# MotherboardRev1.net
KiCad netlist of a schematic drawn in EAGLE
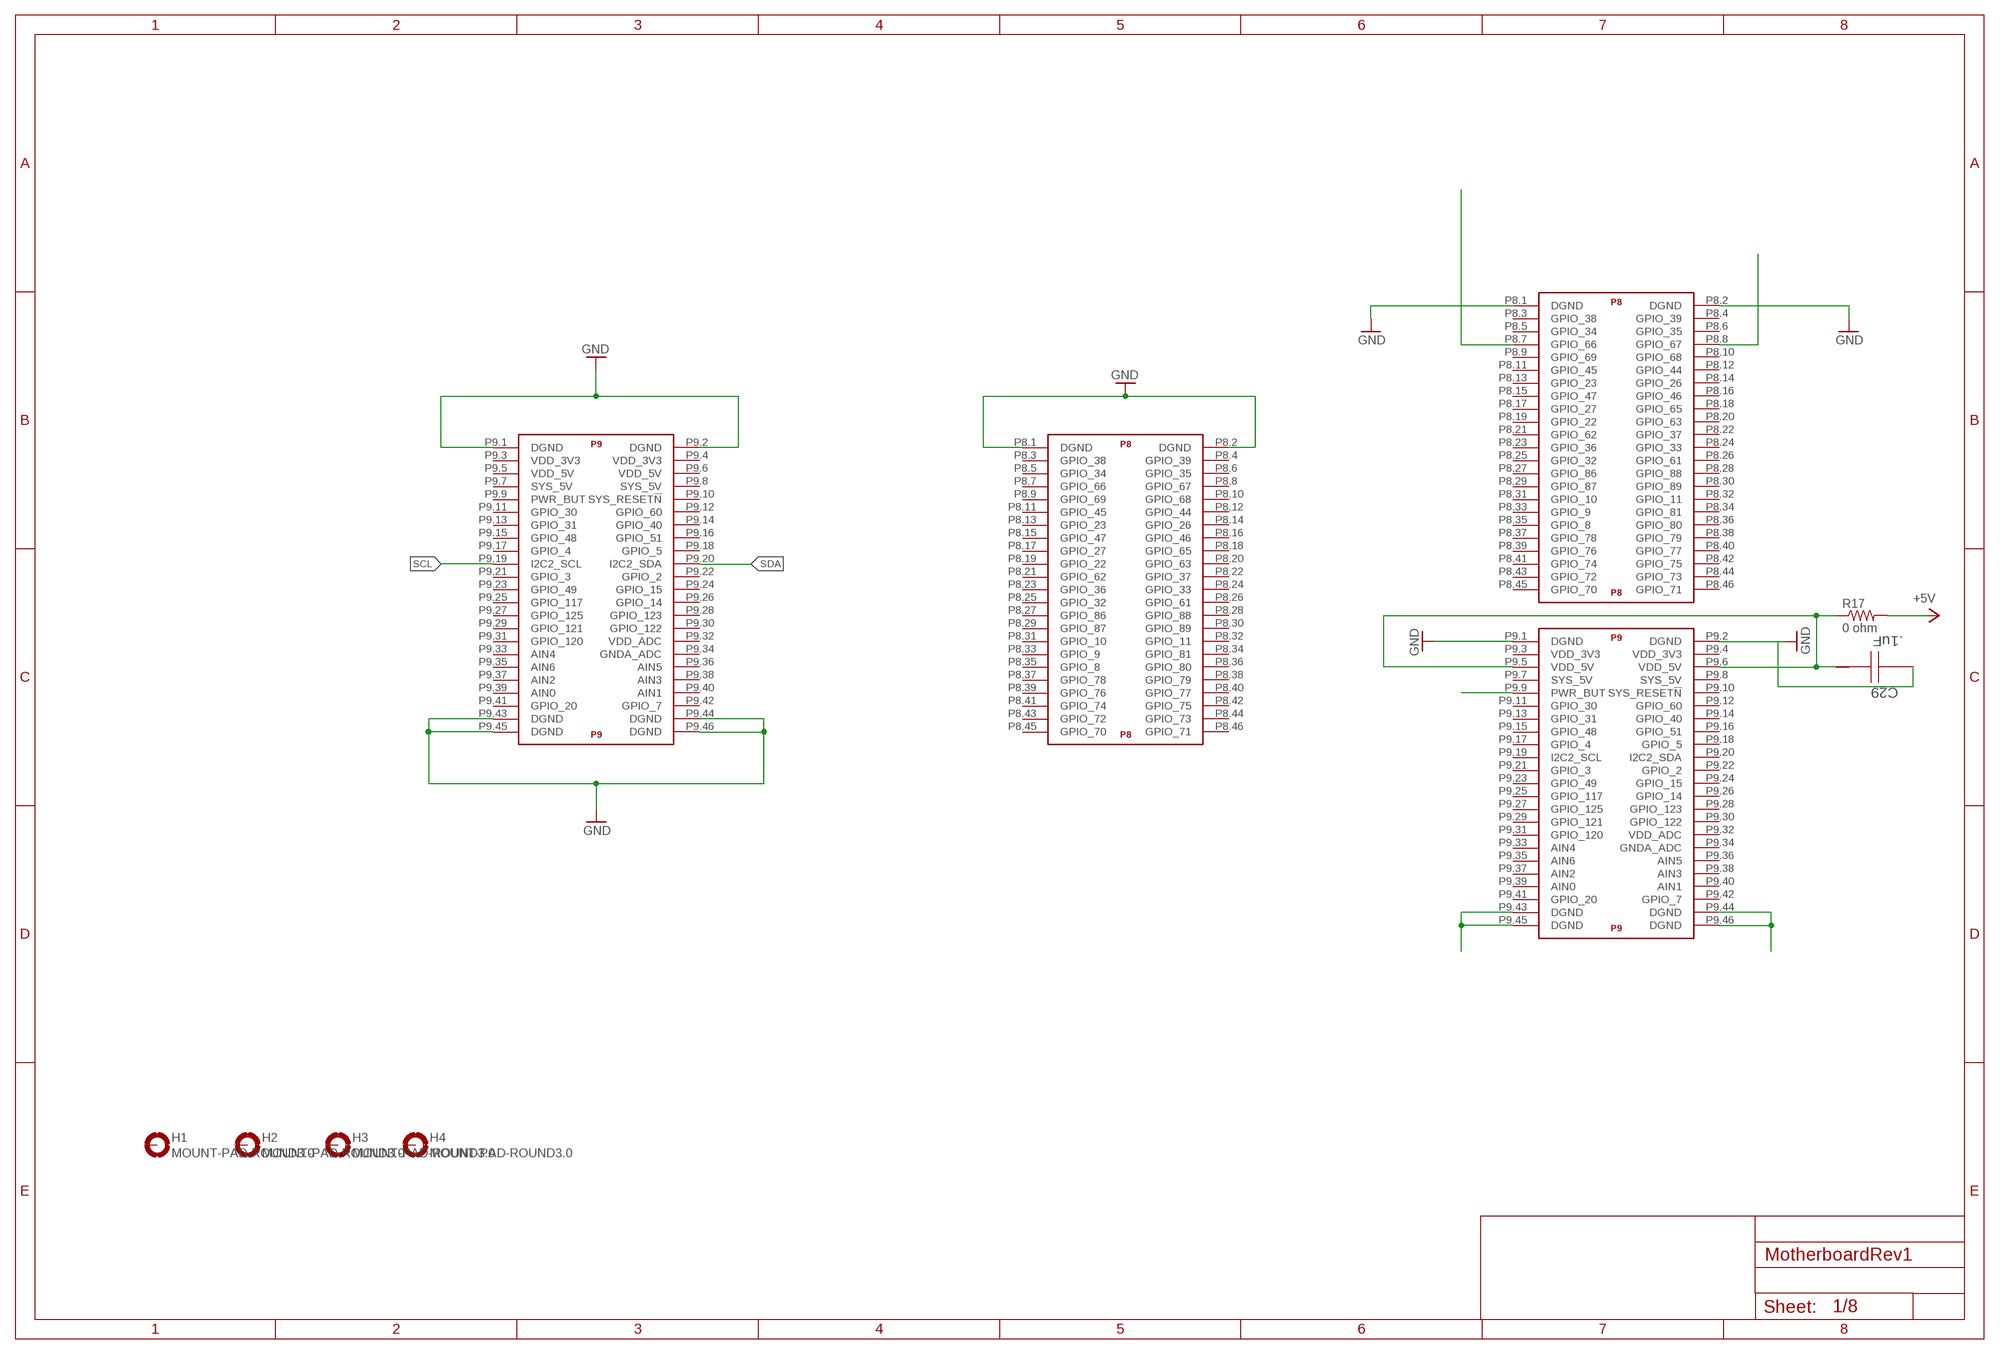
[diagram p0: schematic, sheet 1]
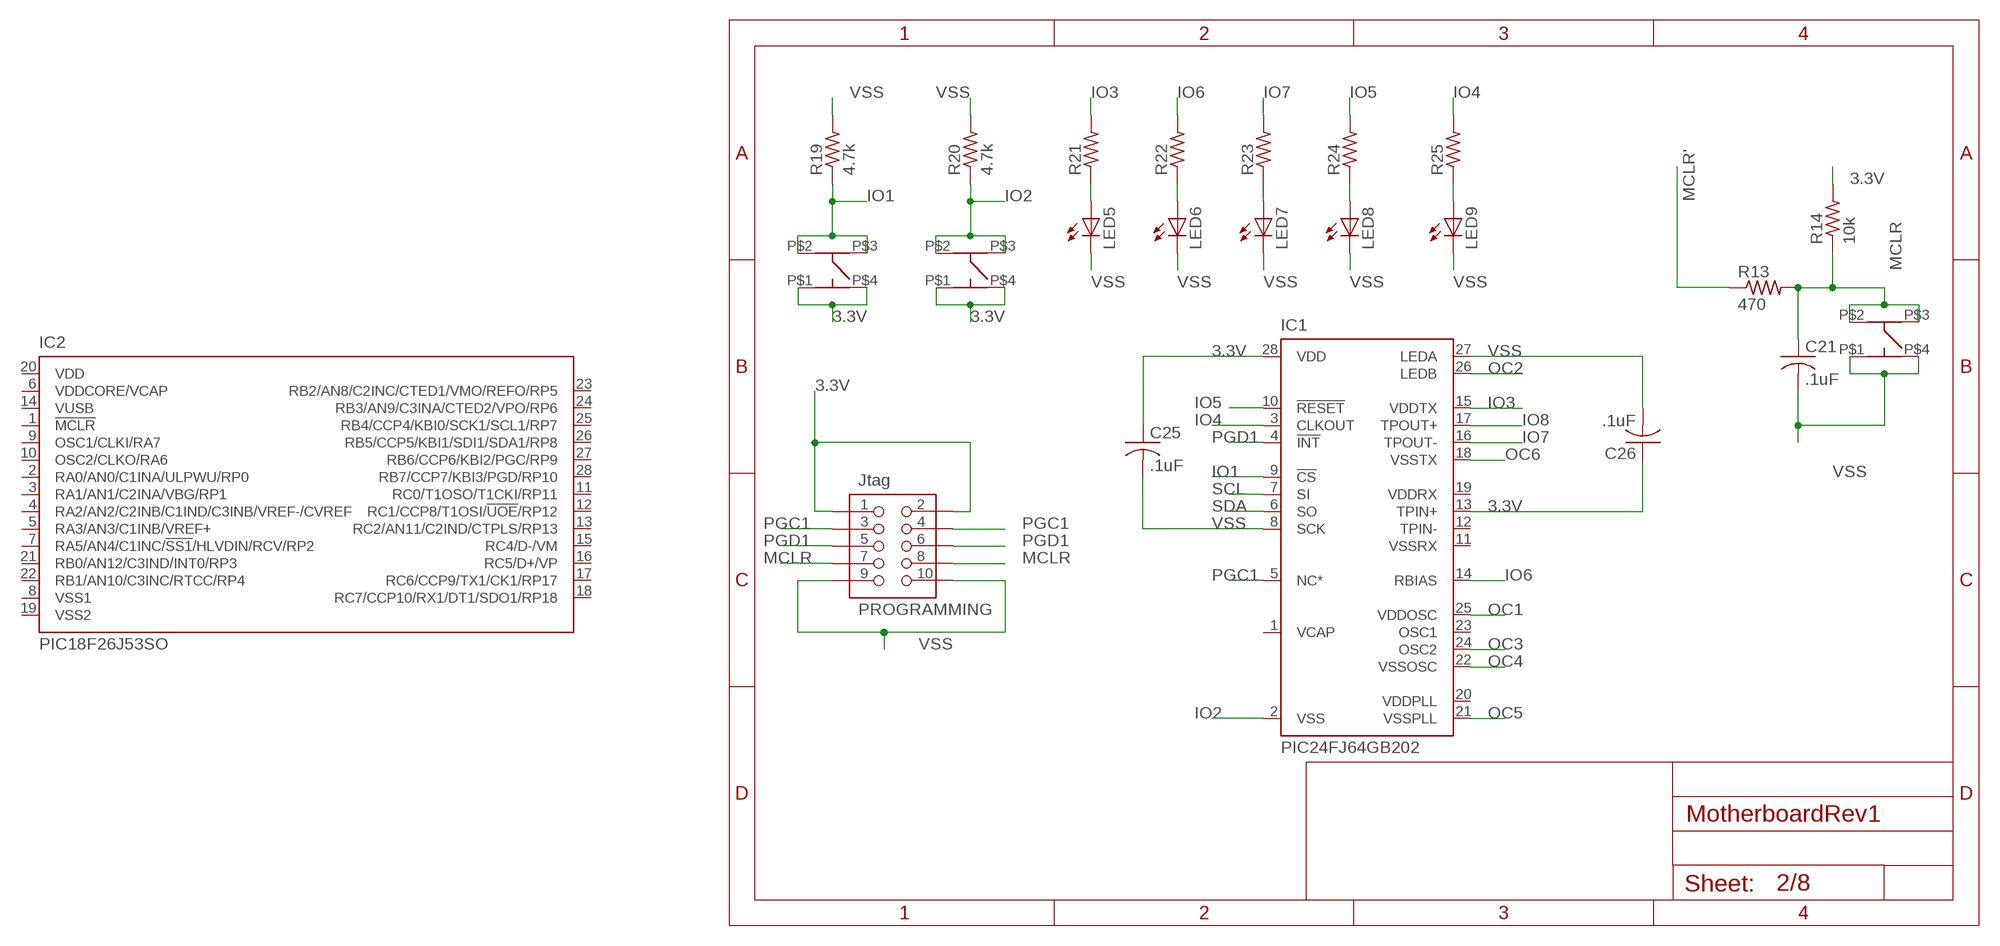
[diagram p1: schematic, sheet 2]
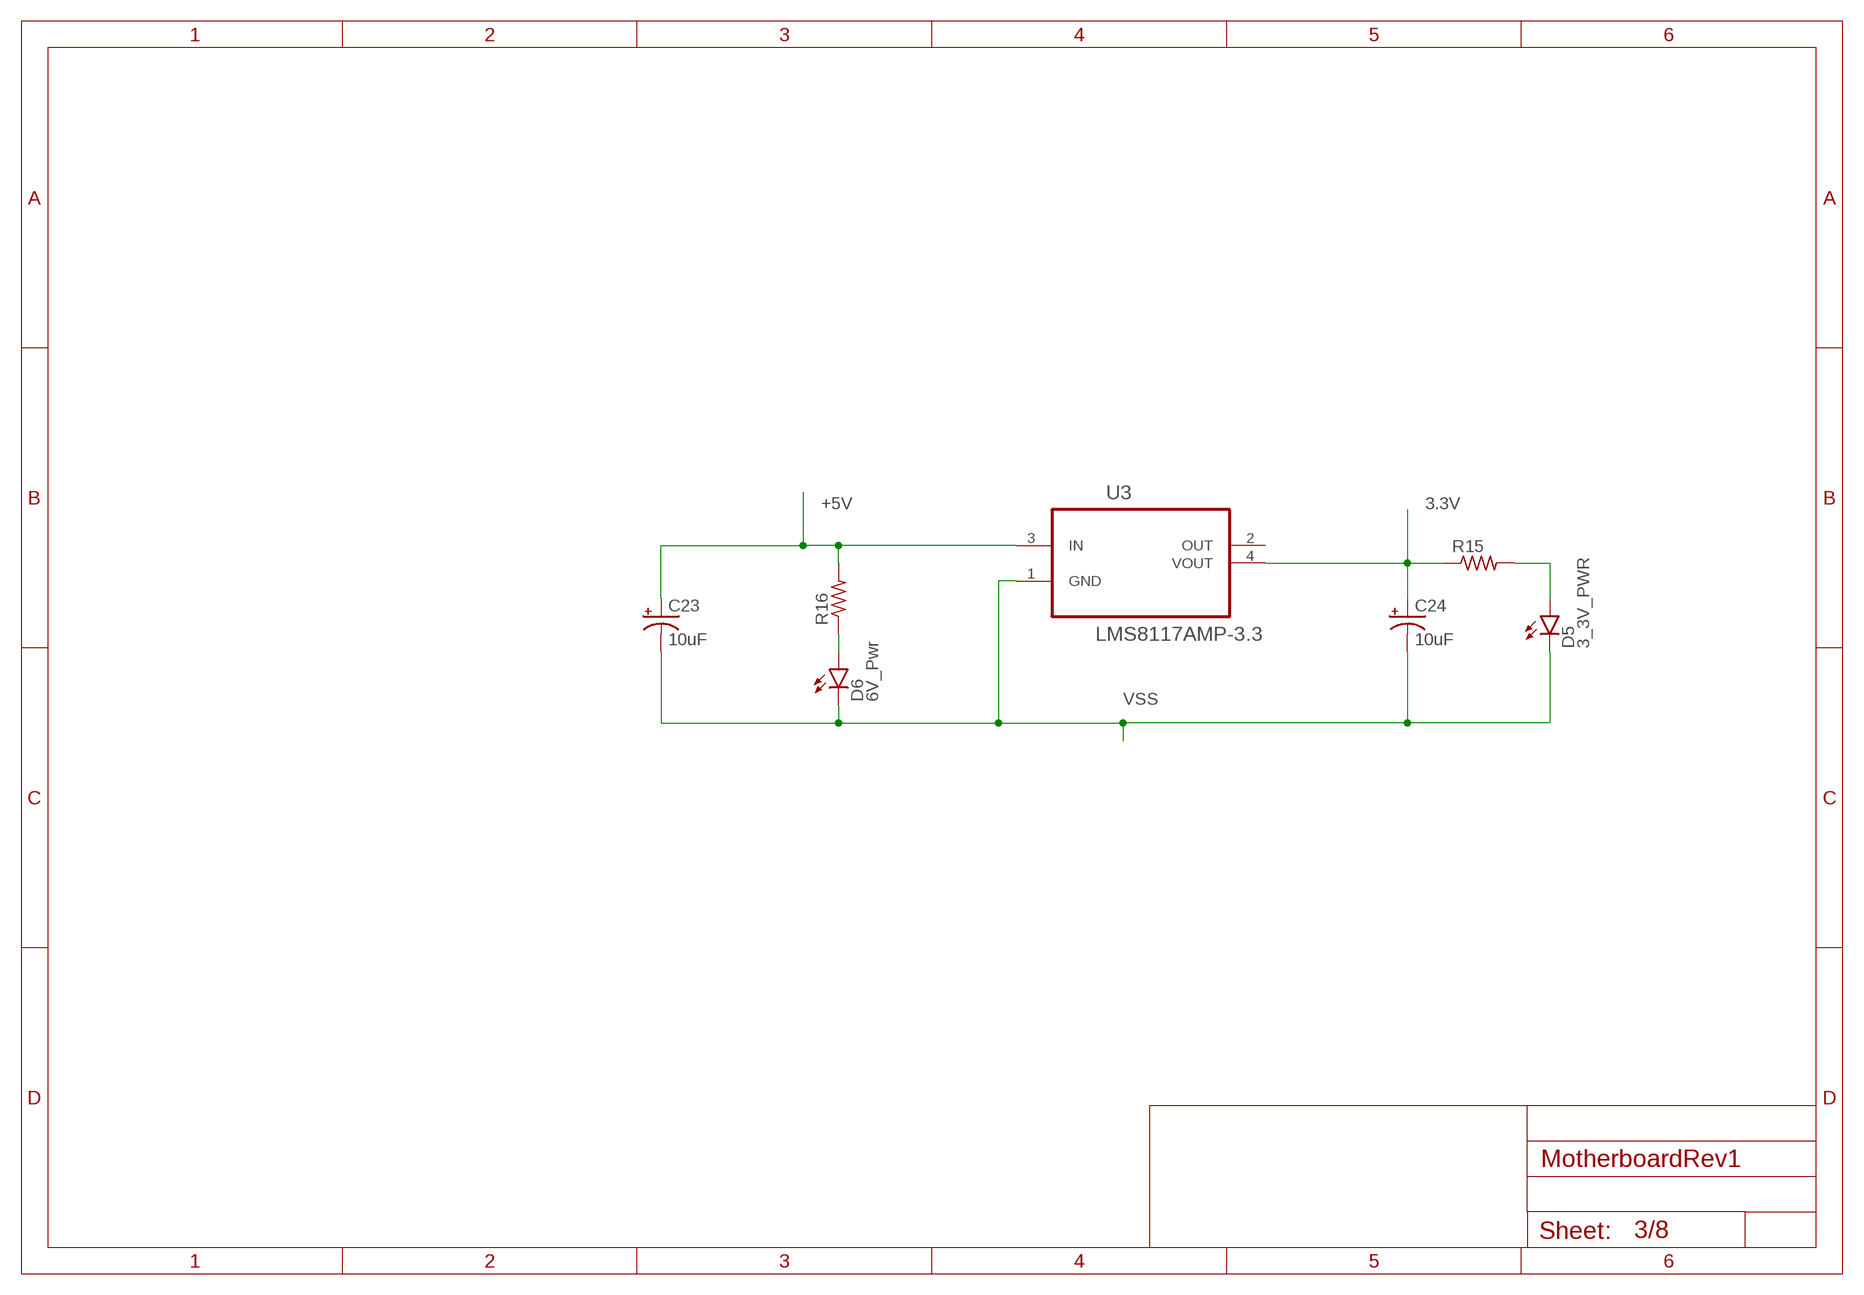
[diagram p2: schematic, sheet 3]
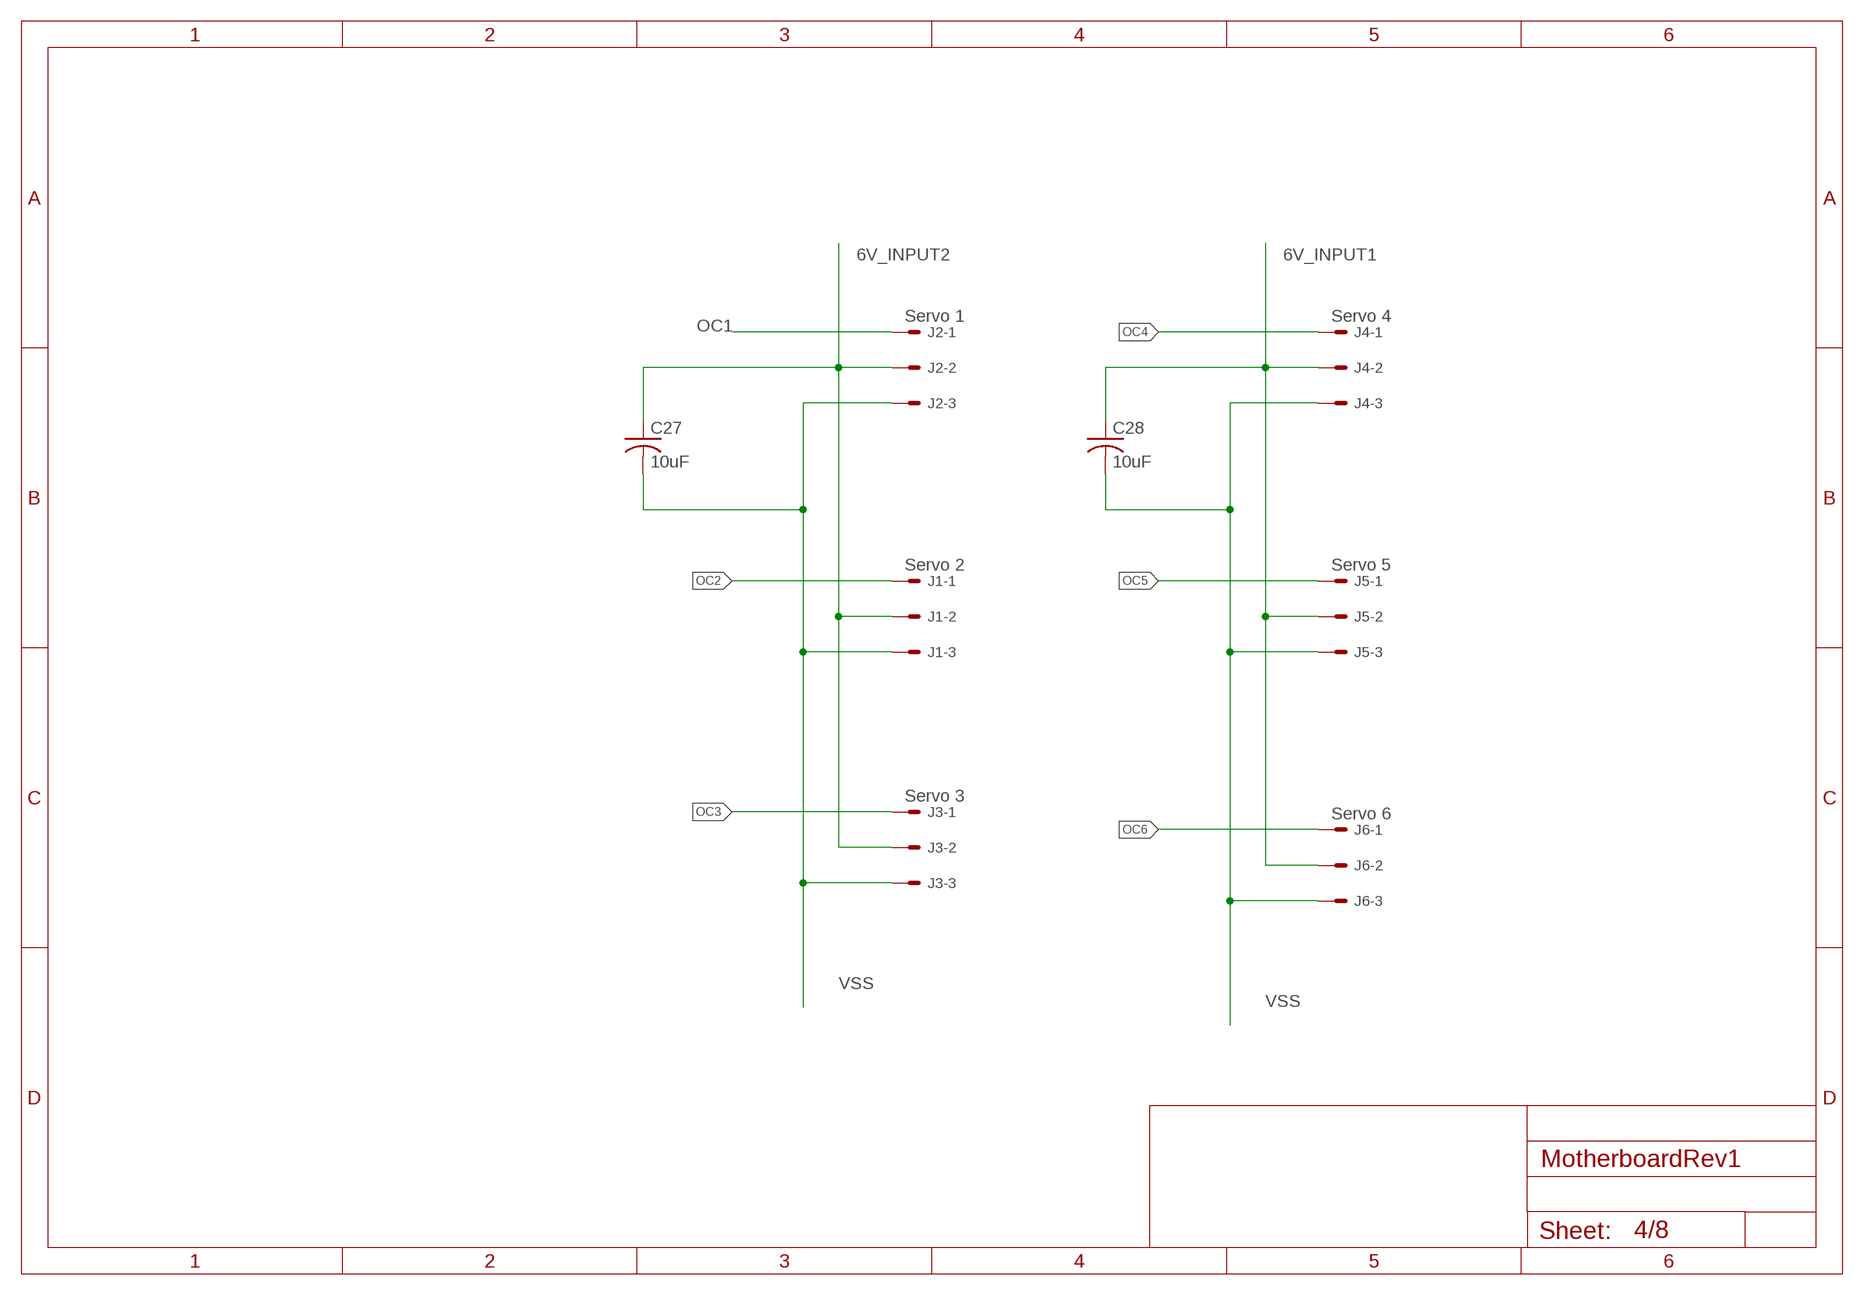
[diagram p3: schematic, sheet 4]
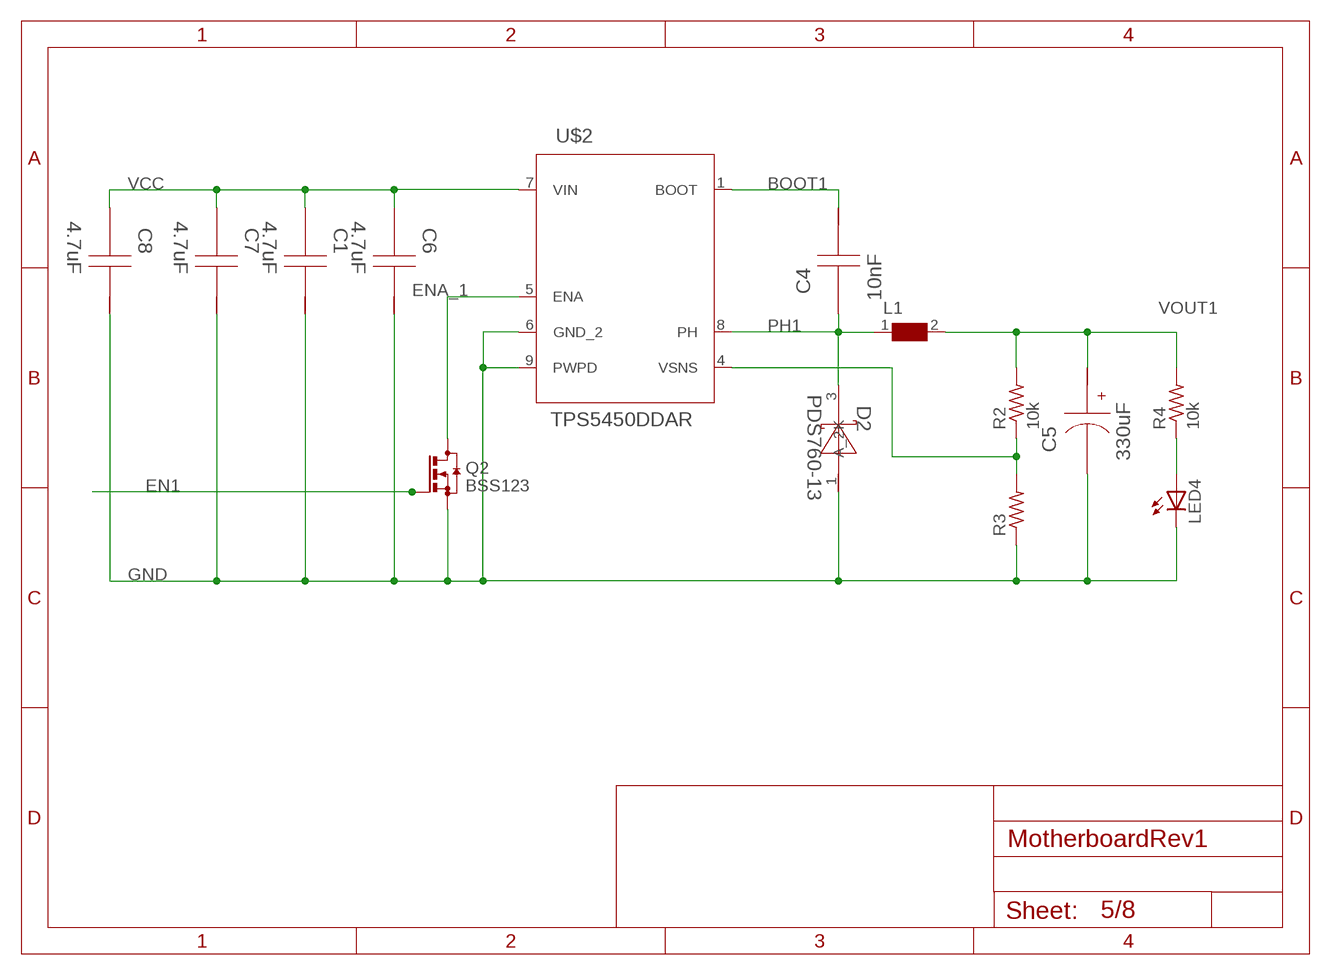
[diagram p4: schematic, sheet 5]
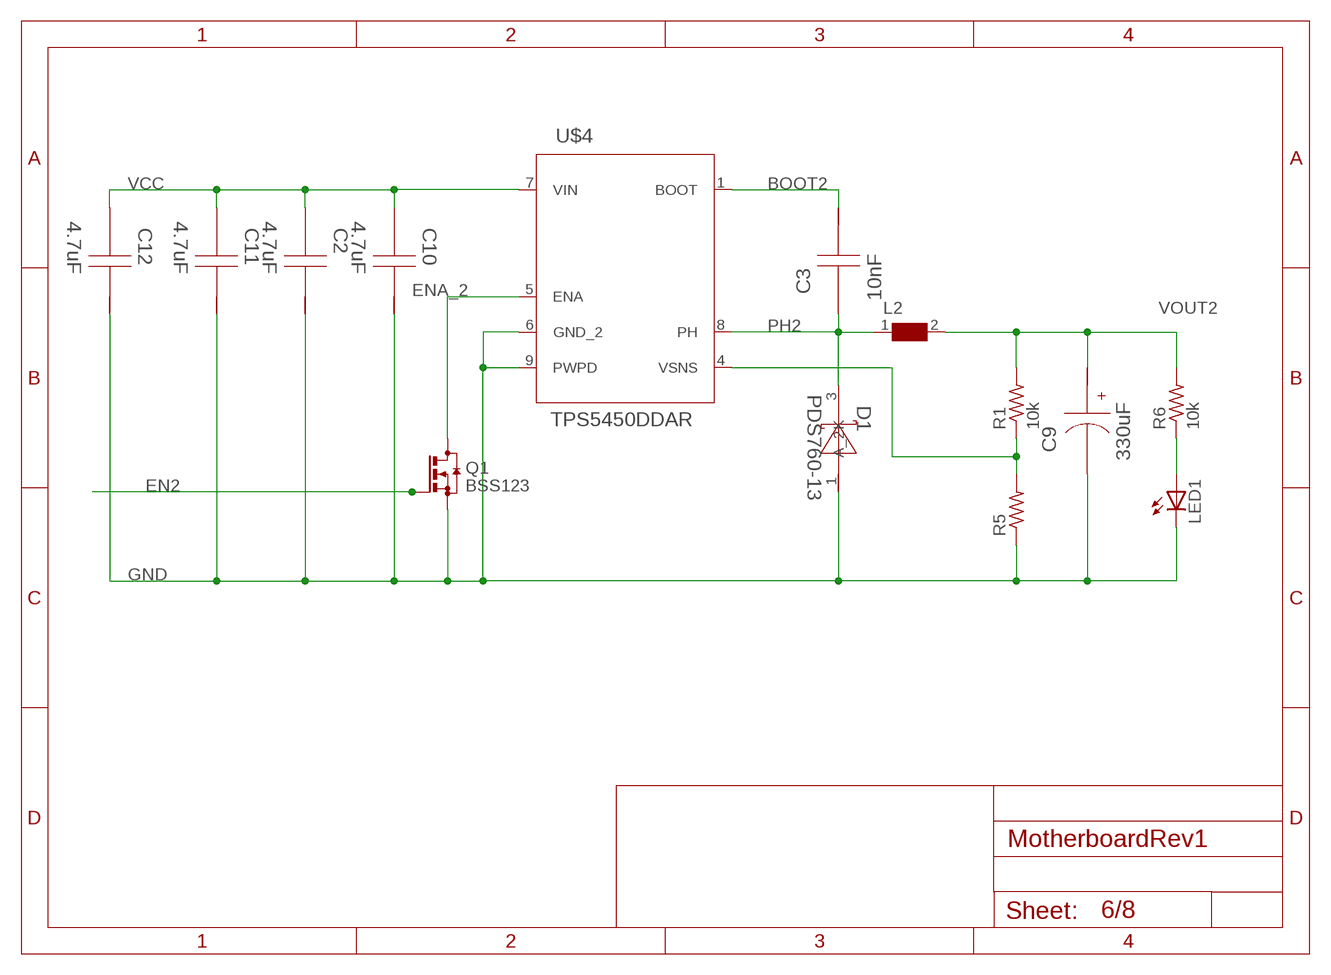
[diagram p5: schematic, sheet 6]
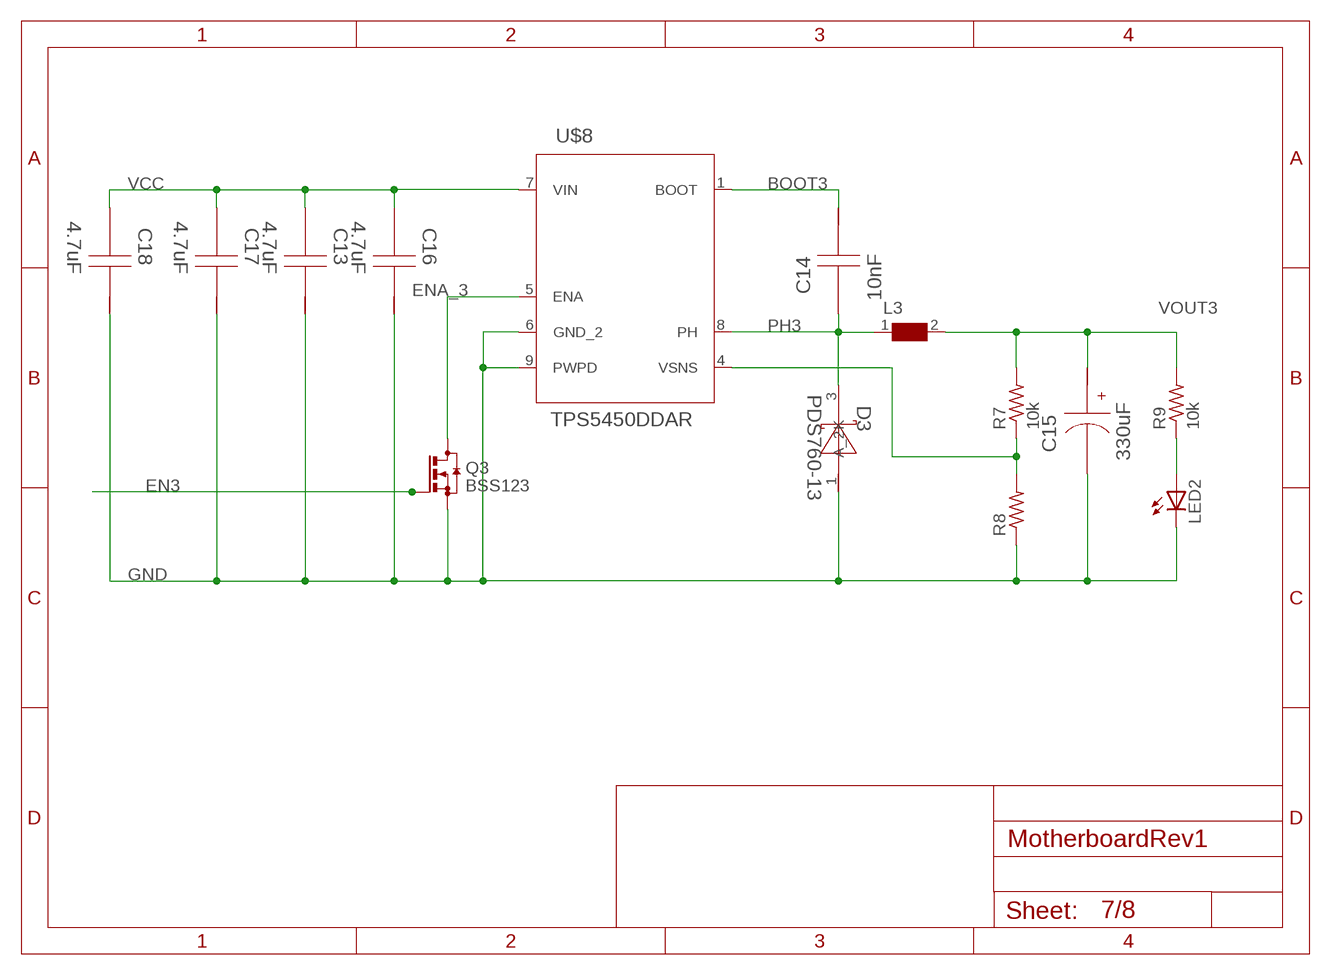
[diagram p6: schematic, sheet 7]
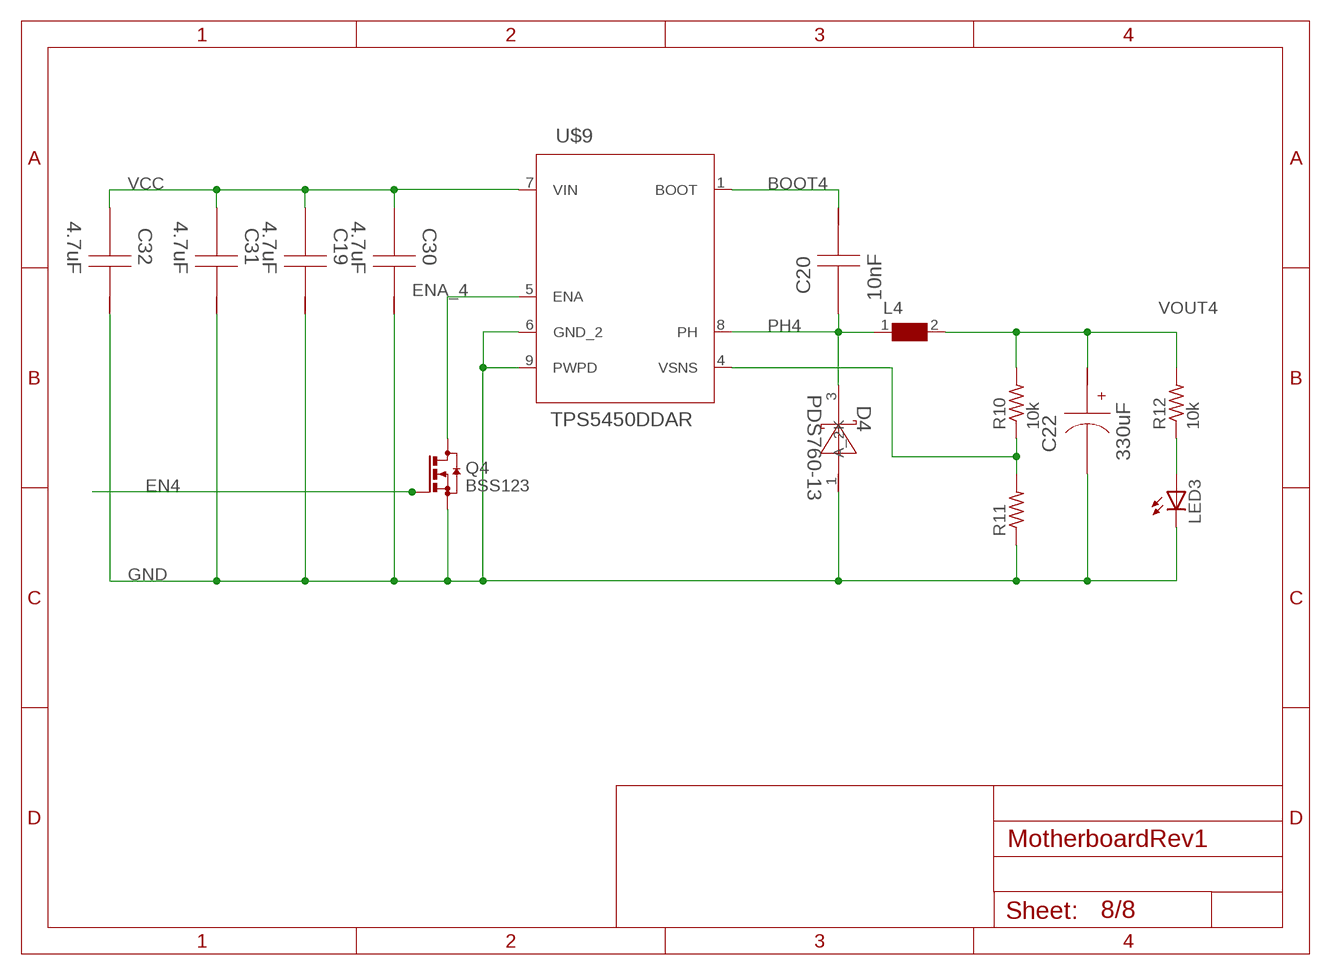
[diagram p7: schematic, sheet 8]

(export (version "E")
  (design (tool "Eeschema 10.0.6"))
  (components
    (comp (ref "C29")
      (value ".1uF")
      (footprint "eagle-import:1206")
      (fields (field (name "MANUFACTURER_PART_NUMBER") "C3216X5R1A106K"))
      (libsource (lib "eagle-import") (part "C3216X5R1A106K"))
    )
    (comp (ref "H1")
      (value "MOUNT-PAD-ROUND3.0")
      (footprint "eagle-import:3,0-PAD")
      (libsource (lib "eagle-import") (part "MOUNT-PAD-ROUND3.0"))
    )
    (comp (ref "H2")
      (value "MOUNT-PAD-ROUND3.0")
      (footprint "eagle-import:3,0-PAD")
      (libsource (lib "eagle-import") (part "MOUNT-PAD-ROUND3.0"))
    )
    (comp (ref "H3")
      (value "MOUNT-PAD-ROUND3.0")
      (footprint "eagle-import:3,0-PAD")
      (libsource (lib "eagle-import") (part "MOUNT-PAD-ROUND3.0"))
    )
    (comp (ref "H4")
      (value "MOUNT-PAD-ROUND3.0")
      (footprint "eagle-import:3,0-PAD")
      (libsource (lib "eagle-import") (part "MOUNT-PAD-ROUND3.0"))
    )
    (comp (ref "R17")
      (value "0 ohm")
      (footprint "eagle-import:R1206")
      (libsource (lib "eagle-import") (part "R-US_R1206"))
    )
    (comp (ref "U$1")
      (value "BEAGLE_BONE_BLACK_CAPE")
      (footprint "eagle-import:BEAGLE_BONE_BLACK_CAPE")
      (libsource (lib "eagle-import") (part "BEAGLE_BONE_BLACK_CAPE"))
    )
    (comp (ref "U$3")
      (value "BEAGLE_BONE_BLACK_CAPE")
      (footprint "eagle-import:BEAGLE_BONE_BLACK_CAPE")
      (libsource (lib "eagle-import") (part "SparkFun-Boards_BEAGLE_BONE_BLACK_CAPE"))
    )
    (comp (ref "C21")
      (value ".1uF")
      (footprint "eagle-import:C0805")
      (libsource (lib "eagle-import") (part "C-USC0805"))
    )
    (comp (ref "C25")
      (value ".1uF")
      (footprint "eagle-import:C0805")
      (libsource (lib "eagle-import") (part "C-USC0805"))
    )
    (comp (ref "C26")
      (value ".1uF")
      (footprint "eagle-import:C0805")
      (libsource (lib "eagle-import") (part "C-USC0805"))
    )
    (comp (ref "IC1")
      (value "PIC24FJ64GB202")
      (footprint "eagle-import:DIL28-3")
      (fields (field (name "MF") "MICROCHIP") (field (name "MPN") "ENC28J60/SP"))
      (libsource (lib "eagle-import") (part "ENC28J60SP"))
    )
    (comp (ref "IC2")
      (value "PIC18F26J53SO")
      (footprint "eagle-import:SO28W")
      (fields (field (name "MPN") "PIC18F26J53-I/SO"))
      (libsource (lib "eagle-import") (part "PIC18F2J53SO6"))
    )
    (comp (ref "LED5")
      (value "LED_LEDCHIPLED_1206")
      (footprint "eagle-import:LED_CHIPLED_1206")
      (libsource (lib "eagle-import") (part "LED_LEDCHIPLED_1206"))
    )
    (comp (ref "LED6")
      (value "LED_LEDCHIPLED_1206")
      (footprint "eagle-import:LED_CHIPLED_1206")
      (libsource (lib "eagle-import") (part "LED_LEDCHIPLED_1206"))
    )
    (comp (ref "LED7")
      (value "LED_LEDCHIPLED_1206")
      (footprint "eagle-import:LED_CHIPLED_1206")
      (libsource (lib "eagle-import") (part "LED_LEDCHIPLED_1206"))
    )
    (comp (ref "LED8")
      (value "LED_LEDCHIPLED_1206")
      (footprint "eagle-import:LED_CHIPLED_1206")
      (libsource (lib "eagle-import") (part "LED_LEDCHIPLED_1206"))
    )
    (comp (ref "LED9")
      (value "LED_LEDCHIPLED_1206")
      (footprint "eagle-import:LED_CHIPLED_1206")
      (libsource (lib "eagle-import") (part "LED_LEDCHIPLED_1206"))
    )
    (comp (ref "PROGRAMMING")
      (value "Jtag")
      (footprint "eagle-import:MOTHER-BOARD-REV5_10-PIN-SMD")
      (libsource (lib "eagle-import") (part "MOTHER-BOARD-REV5_PIN-CONNECTOR74089"))
    )
    (comp (ref "R13")
      (value "470")
      (footprint "eagle-import:R0805")
      (libsource (lib "eagle-import") (part "R-US_R0805"))
    )
    (comp (ref "R14")
      (value "10k")
      (footprint "eagle-import:R0805")
      (libsource (lib "eagle-import") (part "R-US_R0805"))
    )
    (comp (ref "R19")
      (value "4.7k")
      (footprint "eagle-import:R0805")
      (libsource (lib "eagle-import") (part "R-US_R0805"))
    )
    (comp (ref "R20")
      (value "4.7k")
      (footprint "eagle-import:R0805")
      (libsource (lib "eagle-import") (part "R-US_R0805"))
    )
    (comp (ref "R21")
      (value "R-US_M0805")
      (footprint "eagle-import:M0805")
      (libsource (lib "eagle-import") (part "R-US_M0805"))
    )
    (comp (ref "R22")
      (value "R-US_M0805")
      (footprint "eagle-import:M0805")
      (libsource (lib "eagle-import") (part "R-US_M0805"))
    )
    (comp (ref "R23")
      (value "R-US_M0805")
      (footprint "eagle-import:M0805")
      (libsource (lib "eagle-import") (part "R-US_M0805"))
    )
    (comp (ref "R24")
      (value "R-US_M0805")
      (footprint "eagle-import:M0805")
      (libsource (lib "eagle-import") (part "R-US_M0805"))
    )
    (comp (ref "R25")
      (value "R-US_M0805")
      (footprint "eagle-import:M0805")
      (libsource (lib "eagle-import") (part "R-US_M0805"))
    )
    (comp (ref "U$5")
      (value "Switch3")
      (footprint "eagle-import:MC32882_FINAL")
      (libsource (lib "eagle-import") (part "MC32882_SW"))
    )
    (comp (ref "U$6")
      (value "Switch1")
      (footprint "eagle-import:MC32882_FINAL")
      (libsource (lib "eagle-import") (part "MC32882_SW"))
    )
    (comp (ref "U$7")
      (value "Switch2")
      (footprint "eagle-import:MC32882_FINAL")
      (libsource (lib "eagle-import") (part "MC32882_SW"))
    )
    (comp (ref "C2")
      (value "4.7uF")
      (footprint "eagle-import:1206")
      (fields (field (name "MANUFACTURER_PART_NUMBER") "GRM31CR71H475KA12L"))
      (libsource (lib "eagle-import") (part "GRM31CR71H475KA12L"))
    )
    (comp (ref "C3")
      (value "10nF")
      (footprint "eagle-import:0805")
      (fields (field (name "MANUFACTURER_PART_NUMBER") "C0805C103K5RACTU"))
      (libsource (lib "eagle-import") (part "C0805C103K5RACTU"))
    )
    (comp (ref "C9")
      (value "330uF")
      (footprint "eagle-import:SM_RADIAL_10AMM")
      (fields (field (name "MANUFACTURER_PART_NUMBER") "10SVP330MX"))
      (libsource (lib "eagle-import") (part "10SVP330MX"))
    )
    (comp (ref "C10")
      (value "4.7uF")
      (footprint "eagle-import:1206")
      (fields (field (name "MANUFACTURER_PART_NUMBER") "GRM31CR71H475KA12L"))
      (libsource (lib "eagle-import") (part "GRM31CR71H475KA12L"))
    )
    (comp (ref "C11")
      (value "4.7uF")
      (footprint "eagle-import:1206")
      (fields (field (name "MANUFACTURER_PART_NUMBER") "GRM31CR71H475KA12L"))
      (libsource (lib "eagle-import") (part "GRM31CR71H475KA12L"))
    )
    (comp (ref "C12")
      (value "4.7uF")
      (footprint "eagle-import:1206")
      (fields (field (name "MANUFACTURER_PART_NUMBER") "GRM31CR71H475KA12L"))
      (libsource (lib "eagle-import") (part "GRM31CR71H475KA12L"))
    )
    (comp (ref "D1")
      (value "PDS760-13")
      (footprint "eagle-import:POWERDI5")
      (libsource (lib "eagle-import") (part "PDS760-13"))
    )
    (comp (ref "L2")
      (value "WE-HCC-7443331000_1090")
      (footprint "eagle-import:WE-HCC_1090")
      (fields (field (name "MPN") "7443331000"))
      (libsource (lib "eagle-import") (part "WE-HCC_1090-7443331000"))
    )
    (comp (ref "LED1")
      (value "LEDSML1206")
      (footprint "eagle-import:SML1206")
      (libsource (lib "eagle-import") (part "LEDSML1206"))
    )
    (comp (ref "Q1")
      (value "BSS123")
      (footprint "eagle-import:SOT23")
      (libsource (lib "eagle-import") (part "BSS123"))
    )
    (comp (ref "R1")
      (value "10k")
      (footprint "eagle-import:R1206")
      (libsource (lib "eagle-import") (part "R-US_R1206"))
    )
    (comp (ref "R5")
      (value "R-US_R1206")
      (footprint "eagle-import:R1206")
      (libsource (lib "eagle-import") (part "R-US_R1206"))
    )
    (comp (ref "R6")
      (value "10k")
      (footprint "eagle-import:R1206")
      (libsource (lib "eagle-import") (part "R-US_R1206"))
    )
    (comp (ref "U$4")
      (value "TPS5450DDAR")
      (footprint "eagle-import:R-PDSO-G8")
      (fields (field (name "MANUFACTURER_PART_NUMBER") "TPS5450DDA"))
      (libsource (lib "eagle-import") (part "TPS5450DDAR"))
    )
    (comp (ref "C19")
      (value "4.7uF")
      (footprint "eagle-import:1206")
      (fields (field (name "MANUFACTURER_PART_NUMBER") "GRM31CR71H475KA12L"))
      (libsource (lib "eagle-import") (part "GRM31CR71H475KA12L"))
    )
    (comp (ref "C20")
      (value "10nF")
      (footprint "eagle-import:0805")
      (fields (field (name "MANUFACTURER_PART_NUMBER") "C0805C103K5RACTU"))
      (libsource (lib "eagle-import") (part "C0805C103K5RACTU"))
    )
    (comp (ref "C22")
      (value "330uF")
      (footprint "eagle-import:SM_RADIAL_10AMM")
      (fields (field (name "MANUFACTURER_PART_NUMBER") "10SVP330MX"))
      (libsource (lib "eagle-import") (part "10SVP330MX"))
    )
    (comp (ref "C30")
      (value "4.7uF")
      (footprint "eagle-import:1206")
      (fields (field (name "MANUFACTURER_PART_NUMBER") "GRM31CR71H475KA12L"))
      (libsource (lib "eagle-import") (part "GRM31CR71H475KA12L"))
    )
    (comp (ref "C31")
      (value "4.7uF")
      (footprint "eagle-import:1206")
      (fields (field (name "MANUFACTURER_PART_NUMBER") "GRM31CR71H475KA12L"))
      (libsource (lib "eagle-import") (part "GRM31CR71H475KA12L"))
    )
    (comp (ref "C32")
      (value "4.7uF")
      (footprint "eagle-import:1206")
      (fields (field (name "MANUFACTURER_PART_NUMBER") "GRM31CR71H475KA12L"))
      (libsource (lib "eagle-import") (part "GRM31CR71H475KA12L"))
    )
    (comp (ref "D4")
      (value "PDS760-13")
      (footprint "eagle-import:POWERDI5")
      (libsource (lib "eagle-import") (part "PDS760-13"))
    )
    (comp (ref "L4")
      (value "WE-HCC-7443331000_1090")
      (footprint "eagle-import:WE-HCC_1090")
      (fields (field (name "MPN") "7443331000"))
      (libsource (lib "eagle-import") (part "WE-HCC_1090-7443331000"))
    )
    (comp (ref "LED3")
      (value "LEDSML1206")
      (footprint "eagle-import:SML1206")
      (libsource (lib "eagle-import") (part "LEDSML1206"))
    )
    (comp (ref "Q4")
      (value "BSS123")
      (footprint "eagle-import:SOT23")
      (libsource (lib "eagle-import") (part "BSS123"))
    )
    (comp (ref "R10")
      (value "10k")
      (footprint "eagle-import:R1206")
      (libsource (lib "eagle-import") (part "R-US_R1206"))
    )
    (comp (ref "R11")
      (value "R-US_R1206")
      (footprint "eagle-import:R1206")
      (libsource (lib "eagle-import") (part "R-US_R1206"))
    )
    (comp (ref "R12")
      (value "10k")
      (footprint "eagle-import:R1206")
      (libsource (lib "eagle-import") (part "R-US_R1206"))
    )
    (comp (ref "U$9")
      (value "TPS5450DDAR")
      (footprint "eagle-import:R-PDSO-G8")
      (fields (field (name "MANUFACTURER_PART_NUMBER") "TPS5450DDA"))
      (libsource (lib "eagle-import") (part "TPS5450DDAR"))
    )
    (comp (ref "C13")
      (value "4.7uF")
      (footprint "eagle-import:1206")
      (fields (field (name "MANUFACTURER_PART_NUMBER") "GRM31CR71H475KA12L"))
      (libsource (lib "eagle-import") (part "GRM31CR71H475KA12L"))
    )
    (comp (ref "C14")
      (value "10nF")
      (footprint "eagle-import:0805")
      (fields (field (name "MANUFACTURER_PART_NUMBER") "C0805C103K5RACTU"))
      (libsource (lib "eagle-import") (part "C0805C103K5RACTU"))
    )
    (comp (ref "C15")
      (value "330uF")
      (footprint "eagle-import:SM_RADIAL_10AMM")
      (fields (field (name "MANUFACTURER_PART_NUMBER") "10SVP330MX"))
      (libsource (lib "eagle-import") (part "10SVP330MX"))
    )
    (comp (ref "C16")
      (value "4.7uF")
      (footprint "eagle-import:1206")
      (fields (field (name "MANUFACTURER_PART_NUMBER") "GRM31CR71H475KA12L"))
      (libsource (lib "eagle-import") (part "GRM31CR71H475KA12L"))
    )
    (comp (ref "C17")
      (value "4.7uF")
      (footprint "eagle-import:1206")
      (fields (field (name "MANUFACTURER_PART_NUMBER") "GRM31CR71H475KA12L"))
      (libsource (lib "eagle-import") (part "GRM31CR71H475KA12L"))
    )
    (comp (ref "C18")
      (value "4.7uF")
      (footprint "eagle-import:1206")
      (fields (field (name "MANUFACTURER_PART_NUMBER") "GRM31CR71H475KA12L"))
      (libsource (lib "eagle-import") (part "GRM31CR71H475KA12L"))
    )
    (comp (ref "D3")
      (value "PDS760-13")
      (footprint "eagle-import:POWERDI5")
      (libsource (lib "eagle-import") (part "PDS760-13"))
    )
    (comp (ref "L3")
      (value "WE-HCC-7443331000_1090")
      (footprint "eagle-import:WE-HCC_1090")
      (fields (field (name "MPN") "7443331000"))
      (libsource (lib "eagle-import") (part "WE-HCC_1090-7443331000"))
    )
    (comp (ref "LED2")
      (value "LEDSML1206")
      (footprint "eagle-import:SML1206")
      (libsource (lib "eagle-import") (part "LEDSML1206"))
    )
    (comp (ref "Q3")
      (value "BSS123")
      (footprint "eagle-import:SOT23")
      (libsource (lib "eagle-import") (part "BSS123"))
    )
    (comp (ref "R7")
      (value "10k")
      (footprint "eagle-import:R1206")
      (libsource (lib "eagle-import") (part "R-US_R1206"))
    )
    (comp (ref "R8")
      (value "R-US_R1206")
      (footprint "eagle-import:R1206")
      (libsource (lib "eagle-import") (part "R-US_R1206"))
    )
    (comp (ref "R9")
      (value "10k")
      (footprint "eagle-import:R1206")
      (libsource (lib "eagle-import") (part "R-US_R1206"))
    )
    (comp (ref "U$8")
      (value "TPS5450DDAR")
      (footprint "eagle-import:R-PDSO-G8")
      (fields (field (name "MANUFACTURER_PART_NUMBER") "TPS5450DDA"))
      (libsource (lib "eagle-import") (part "TPS5450DDAR"))
    )
    (comp (ref "C27")
      (value "10uF")
      (footprint "eagle-import:C0805")
      (libsource (lib "eagle-import") (part "C-USC0805"))
    )
    (comp (ref "C28")
      (value "10uF")
      (footprint "eagle-import:C0805")
      (libsource (lib "eagle-import") (part "C-USC0805"))
    )
    (comp (ref "J1")
      (value "Servo 2")
      (footprint "eagle-import:7395-03")
      (libsource (lib "eagle-import") (part "22-?-0305-7038"))
    )
    (comp (ref "J2")
      (value "Servo 1")
      (footprint "eagle-import:7395-03")
      (libsource (lib "eagle-import") (part "22-?-0305-7038"))
    )
    (comp (ref "J3")
      (value "Servo 3")
      (footprint "eagle-import:7395-03")
      (libsource (lib "eagle-import") (part "22-?-0305-7038"))
    )
    (comp (ref "J4")
      (value "Servo 4")
      (footprint "eagle-import:7395-03")
      (libsource (lib "eagle-import") (part "22-?-0305-7038"))
    )
    (comp (ref "J5")
      (value "Servo 5")
      (footprint "eagle-import:7395-03")
      (libsource (lib "eagle-import") (part "22-?-0305-7038"))
    )
    (comp (ref "J6")
      (value "Servo 6")
      (footprint "eagle-import:7395-03")
      (libsource (lib "eagle-import") (part "22-?-0305-7038"))
    )
    (comp (ref "C1")
      (value "4.7uF")
      (footprint "eagle-import:1206")
      (fields (field (name "MANUFACTURER_PART_NUMBER") "GRM31CR71H475KA12L"))
      (libsource (lib "eagle-import") (part "GRM31CR71H475KA12L"))
    )
    (comp (ref "C4")
      (value "10nF")
      (footprint "eagle-import:0805")
      (fields (field (name "MANUFACTURER_PART_NUMBER") "C0805C103K5RACTU"))
      (libsource (lib "eagle-import") (part "C0805C103K5RACTU"))
    )
    (comp (ref "C5")
      (value "330uF")
      (footprint "eagle-import:SM_RADIAL_10AMM")
      (fields (field (name "MANUFACTURER_PART_NUMBER") "10SVP330MX"))
      (libsource (lib "eagle-import") (part "10SVP330MX"))
    )
    (comp (ref "C6")
      (value "4.7uF")
      (footprint "eagle-import:1206")
      (fields (field (name "MANUFACTURER_PART_NUMBER") "GRM31CR71H475KA12L"))
      (libsource (lib "eagle-import") (part "GRM31CR71H475KA12L"))
    )
    (comp (ref "C7")
      (value "4.7uF")
      (footprint "eagle-import:1206")
      (fields (field (name "MANUFACTURER_PART_NUMBER") "GRM31CR71H475KA12L"))
      (libsource (lib "eagle-import") (part "GRM31CR71H475KA12L"))
    )
    (comp (ref "C8")
      (value "4.7uF")
      (footprint "eagle-import:1206")
      (fields (field (name "MANUFACTURER_PART_NUMBER") "GRM31CR71H475KA12L"))
      (libsource (lib "eagle-import") (part "GRM31CR71H475KA12L"))
    )
    (comp (ref "D2")
      (value "PDS760-13")
      (footprint "eagle-import:POWERDI5")
      (libsource (lib "eagle-import") (part "PDS760-13"))
    )
    (comp (ref "L1")
      (value "WE-HCC-7443331000_1090")
      (footprint "eagle-import:WE-HCC_1090")
      (fields (field (name "MPN") "7443331000"))
      (libsource (lib "eagle-import") (part "WE-HCC_1090-7443331000"))
    )
    (comp (ref "LED4")
      (value "LEDSML1206")
      (footprint "eagle-import:SML1206")
      (libsource (lib "eagle-import") (part "LEDSML1206"))
    )
    (comp (ref "Q2")
      (value "BSS123")
      (footprint "eagle-import:SOT23")
      (libsource (lib "eagle-import") (part "BSS123"))
    )
    (comp (ref "R2")
      (value "10k")
      (footprint "eagle-import:R1206")
      (libsource (lib "eagle-import") (part "R-US_R1206"))
    )
    (comp (ref "R3")
      (value "R-US_R1206")
      (footprint "eagle-import:R1206")
      (libsource (lib "eagle-import") (part "R-US_R1206"))
    )
    (comp (ref "R4")
      (value "10k")
      (footprint "eagle-import:R1206")
      (libsource (lib "eagle-import") (part "R-US_R1206"))
    )
    (comp (ref "U$2")
      (value "TPS5450DDAR")
      (footprint "eagle-import:R-PDSO-G8")
      (fields (field (name "MANUFACTURER_PART_NUMBER") "TPS5450DDA"))
      (libsource (lib "eagle-import") (part "TPS5450DDAR"))
    )
    (comp (ref "C23")
      (value "10uF")
      (footprint "eagle-import:EIA3216")
      (libsource (lib "eagle-import") (part "10UF-16V-10%(TANT)"))
    )
    (comp (ref "C24")
      (value "10uF")
      (footprint "eagle-import:EIA3216")
      (libsource (lib "eagle-import") (part "10UF-16V-10%(TANT)"))
    )
    (comp (ref "D5")
      (value "3_3V_PWR")
      (footprint "eagle-import:FKIT-LED-1206")
      (libsource (lib "eagle-import") (part "LED-FKIT-1206"))
    )
    (comp (ref "D6")
      (value "6V_Pwr")
      (footprint "eagle-import:FKIT-LED-1206")
      (libsource (lib "eagle-import") (part "LED-FKIT-1206"))
    )
    (comp (ref "R15")
      (value "R-US_R0805W")
      (footprint "eagle-import:R0805W")
      (libsource (lib "eagle-import") (part "R-US_R0805W"))
    )
    (comp (ref "R16")
      (value "R-US_R0805W")
      (footprint "eagle-import:R0805W")
      (libsource (lib "eagle-import") (part "R-US_R0805W"))
    )
    (comp (ref "U3")
      (value "LMS8117AMP-3.3")
      (footprint "eagle-import:SOT230P696X180-4N")
      (libsource (lib "eagle-import") (part "LMS8117AMP-3.3"))
    )
  )
  (nets
    (net (code "1") (name "+5V") (class "Default")
      (node (ref "C23") (pin "A") (pinfunction "+_A") (pintype "passive"))
      (node (ref "R16") (pin "2") (pinfunction "2_2") (pintype "passive"))
      (node (ref "R17") (pin "2") (pinfunction "2_2") (pintype "passive"))
      (node (ref "U3") (pin "3") (pinfunction "IN_3") (pintype "power_in"))
    )
    (net (code "2") (name "3.3V") (class "Default")
      (node (ref "C24") (pin "A") (pinfunction "+_A") (pintype "passive"))
      (node (ref "C25") (pin "1") (pinfunction "1_1") (pintype "passive"))
      (node (ref "C26") (pin "1") (pinfunction "1_1") (pintype "passive"))
      (node (ref "IC1") (pin "13") (pinfunction "TPIN+_13") (pintype "input"))
      (node (ref "IC1") (pin "28") (pinfunction "VDD_28") (pintype "input"))
      (node (ref "PROGRAMMING") (pin "1") (pinfunction "P$1_1") (pintype "power_in"))
      (node (ref "PROGRAMMING") (pin "2") (pinfunction "P$2_2") (pintype "power_in"))
      (node (ref "R14") (pin "2") (pinfunction "2_2") (pintype "passive"))
      (node (ref "R15") (pin "1") (pinfunction "1_1") (pintype "passive"))
      (node (ref "U$6") (pin "P$1") (pinfunction "P1_P$1") (pintype "bidirectional"))
      (node (ref "U$6") (pin "P$4") (pinfunction "P4_P$4") (pintype "bidirectional"))
      (node (ref "U$7") (pin "P$1") (pinfunction "P1_P$1") (pintype "bidirectional"))
      (node (ref "U$7") (pin "P$4") (pinfunction "P4_P$4") (pintype "bidirectional"))
      (node (ref "U3") (pin "4") (pinfunction "VOUT_4") (pintype "power_in"))
    )
    (net (code "3") (name "6V_INPUT1") (class "Default")
      (node (ref "C28") (pin "1") (pinfunction "1_1") (pintype "passive"))
      (node (ref "J4") (pin "2") (pinfunction "S_2") (pintype "passive"))
      (node (ref "J5") (pin "2") (pinfunction "S_2") (pintype "passive"))
      (node (ref "J6") (pin "2") (pinfunction "S_2") (pintype "passive"))
    )
    (net (code "4") (name "6V_INPUT2") (class "Default")
      (node (ref "C27") (pin "1") (pinfunction "1_1") (pintype "passive"))
      (node (ref "J1") (pin "2") (pinfunction "S_2") (pintype "passive"))
      (node (ref "J2") (pin "2") (pinfunction "S_2") (pintype "passive"))
      (node (ref "J3") (pin "2") (pinfunction "S_2") (pintype "passive"))
    )
    (net (code "5") (name "BOOT1") (class "Default")
      (node (ref "C4") (pin "1") (pinfunction "1_1") (pintype "passive"))
      (node (ref "U$2") (pin "1") (pinfunction "BOOT_1") (pintype "passive"))
    )
    (net (code "6") (name "BOOT2") (class "Default")
      (node (ref "C3") (pin "1") (pinfunction "1_1") (pintype "passive"))
      (node (ref "U$4") (pin "1") (pinfunction "BOOT_1") (pintype "passive"))
    )
    (net (code "7") (name "BOOT3") (class "Default")
      (node (ref "C14") (pin "1") (pinfunction "1_1") (pintype "passive"))
      (node (ref "U$8") (pin "1") (pinfunction "BOOT_1") (pintype "passive"))
    )
    (net (code "8") (name "BOOT4") (class "Default")
      (node (ref "C20") (pin "1") (pinfunction "1_1") (pintype "passive"))
      (node (ref "U$9") (pin "1") (pinfunction "BOOT_1") (pintype "passive"))
    )
    (net (code "9") (name "EN1") (class "Default")
      (node (ref "Q2") (pin "1") (pinfunction "G_1") (pintype "passive"))
    )
    (net (code "10") (name "EN2") (class "Default")
      (node (ref "Q1") (pin "1") (pinfunction "G_1") (pintype "passive"))
    )
    (net (code "11") (name "EN3") (class "Default")
      (node (ref "Q3") (pin "1") (pinfunction "G_1") (pintype "passive"))
    )
    (net (code "12") (name "EN4") (class "Default")
      (node (ref "Q4") (pin "1") (pinfunction "G_1") (pintype "passive"))
    )
    (net (code "13") (name "ENA_1") (class "Default")
      (node (ref "Q2") (pin "3") (pinfunction "D_3") (pintype "passive"))
      (node (ref "U$2") (pin "5") (pinfunction "ENA_5") (pintype "passive"))
    )
    (net (code "14") (name "ENA_2") (class "Default")
      (node (ref "Q1") (pin "3") (pinfunction "D_3") (pintype "passive"))
      (node (ref "U$4") (pin "5") (pinfunction "ENA_5") (pintype "passive"))
    )
    (net (code "15") (name "ENA_3") (class "Default")
      (node (ref "Q3") (pin "3") (pinfunction "D_3") (pintype "passive"))
      (node (ref "U$8") (pin "5") (pinfunction "ENA_5") (pintype "passive"))
    )
    (net (code "16") (name "ENA_4") (class "Default")
      (node (ref "Q4") (pin "3") (pinfunction "D_3") (pintype "passive"))
      (node (ref "U$9") (pin "5") (pinfunction "ENA_5") (pintype "passive"))
    )
    (net (code "17") (name "GND") (class "Default")
      (node (ref "C1") (pin "1") (pinfunction "1_1") (pintype "passive"))
      (node (ref "C10") (pin "1") (pinfunction "1_1") (pintype "passive"))
      (node (ref "C11") (pin "1") (pinfunction "1_1") (pintype "passive"))
      (node (ref "C12") (pin "1") (pinfunction "1_1") (pintype "passive"))
      (node (ref "C13") (pin "1") (pinfunction "1_1") (pintype "passive"))
      (node (ref "C15") (pin "2") (pinfunction "-_2") (pintype "passive"))
      (node (ref "C16") (pin "1") (pinfunction "1_1") (pintype "passive"))
      (node (ref "C17") (pin "1") (pinfunction "1_1") (pintype "passive"))
      (node (ref "C18") (pin "1") (pinfunction "1_1") (pintype "passive"))
      (node (ref "C19") (pin "1") (pinfunction "1_1") (pintype "passive"))
      (node (ref "C2") (pin "1") (pinfunction "1_1") (pintype "passive"))
      (node (ref "C22") (pin "2") (pinfunction "-_2") (pintype "passive"))
      (node (ref "C29") (pin "2") (pinfunction "2_2") (pintype "passive"))
      (node (ref "C30") (pin "1") (pinfunction "1_1") (pintype "passive"))
      (node (ref "C31") (pin "1") (pinfunction "1_1") (pintype "passive"))
      (node (ref "C32") (pin "1") (pinfunction "1_1") (pintype "passive"))
      (node (ref "C5") (pin "2") (pinfunction "-_2") (pintype "passive"))
      (node (ref "C6") (pin "1") (pinfunction "1_1") (pintype "passive"))
      (node (ref "C7") (pin "1") (pinfunction "1_1") (pintype "passive"))
      (node (ref "C8") (pin "1") (pinfunction "1_1") (pintype "passive"))
      (node (ref "C9") (pin "2") (pinfunction "-_2") (pintype "passive"))
      (node (ref "D1") (pin "1") (pinfunction "A_2_1") (pintype "passive"))
      (node (ref "D2") (pin "1") (pinfunction "A_2_1") (pintype "passive"))
      (node (ref "D3") (pin "1") (pinfunction "A_2_1") (pintype "passive"))
      (node (ref "D4") (pin "1") (pinfunction "A_2_1") (pintype "passive"))
      (node (ref "LED1") (pin "C") (pinfunction "C_C") (pintype "passive"))
      (node (ref "LED2") (pin "C") (pinfunction "C_C") (pintype "passive"))
      (node (ref "LED3") (pin "C") (pinfunction "C_C") (pintype "passive"))
      (node (ref "LED4") (pin "C") (pinfunction "C_C") (pintype "passive"))
      (node (ref "Q1") (pin "2") (pinfunction "S_2") (pintype "passive"))
      (node (ref "Q2") (pin "2") (pinfunction "S_2") (pintype "passive"))
      (node (ref "Q3") (pin "2") (pinfunction "S_2") (pintype "passive"))
      (node (ref "Q4") (pin "2") (pinfunction "S_2") (pintype "passive"))
      (node (ref "R11") (pin "1") (pinfunction "1_1") (pintype "passive"))
      (node (ref "R3") (pin "1") (pinfunction "1_1") (pintype "passive"))
      (node (ref "R5") (pin "1") (pinfunction "1_1") (pintype "passive"))
      (node (ref "R8") (pin "1") (pinfunction "1_1") (pintype "passive"))
      (node (ref "U$1") (pin "P8.1") (pinfunction "DGND_P8.1") (pintype "bidirectional"))
      (node (ref "U$1") (pin "P8.2") (pinfunction "DGND_P8.2") (pintype "bidirectional"))
      (node (ref "U$1") (pin "P9.1") (pinfunction "DGND_P9.1") (pintype "bidirectional"))
      (node (ref "U$1") (pin "P9.2") (pinfunction "DGND_P9.2") (pintype "bidirectional"))
      (node (ref "U$1") (pin "P9.43") (pinfunction "DGND_P9.43") (pintype "bidirectional"))
      (node (ref "U$1") (pin "P9.44") (pinfunction "DGND_P9.44") (pintype "bidirectional"))
      (node (ref "U$1") (pin "P9.45") (pinfunction "DGND_P9.45") (pintype "bidirectional"))
      (node (ref "U$1") (pin "P9.46") (pinfunction "DGND_P9.46") (pintype "bidirectional"))
      (node (ref "U$2") (pin "6") (pinfunction "GND_2_6") (pintype "passive"))
      (node (ref "U$2") (pin "9") (pinfunction "PWPD_9") (pintype "passive"))
      (node (ref "U$3") (pin "P8.1") (pinfunction "DGND_P8.1") (pintype "bidirectional"))
      (node (ref "U$3") (pin "P8.2") (pinfunction "DGND_P8.2") (pintype "bidirectional"))
      (node (ref "U$3") (pin "P9.1") (pinfunction "DGND_P9.1") (pintype "bidirectional"))
      (node (ref "U$3") (pin "P9.2") (pinfunction "DGND_P9.2") (pintype "bidirectional"))
      (node (ref "U$3") (pin "P9.43") (pinfunction "DGND_P9.43") (pintype "bidirectional"))
      (node (ref "U$3") (pin "P9.44") (pinfunction "DGND_P9.44") (pintype "bidirectional"))
      (node (ref "U$3") (pin "P9.45") (pinfunction "DGND_P9.45") (pintype "bidirectional"))
      (node (ref "U$3") (pin "P9.46") (pinfunction "DGND_P9.46") (pintype "bidirectional"))
      (node (ref "U$4") (pin "6") (pinfunction "GND_2_6") (pintype "passive"))
      (node (ref "U$4") (pin "9") (pinfunction "PWPD_9") (pintype "passive"))
      (node (ref "U$8") (pin "6") (pinfunction "GND_2_6") (pintype "passive"))
      (node (ref "U$8") (pin "9") (pinfunction "PWPD_9") (pintype "passive"))
      (node (ref "U$9") (pin "6") (pinfunction "GND_2_6") (pintype "passive"))
      (node (ref "U$9") (pin "9") (pinfunction "PWPD_9") (pintype "passive"))
    )
    (net (code "18") (name "IO1") (class "Default")
      (node (ref "IC1") (pin "9") (pinfunction "~{CS}_9") (pintype "input"))
      (node (ref "R19") (pin "1") (pinfunction "1_1") (pintype "passive"))
      (node (ref "U$6") (pin "P$2") (pinfunction "P2_P$2") (pintype "bidirectional"))
      (node (ref "U$6") (pin "P$3") (pinfunction "P3_P$3") (pintype "bidirectional"))
    )
    (net (code "19") (name "IO2") (class "Default")
      (node (ref "IC1") (pin "2") (pinfunction "VSS_2") (pintype "input"))
      (node (ref "R20") (pin "1") (pinfunction "1_1") (pintype "passive"))
      (node (ref "U$7") (pin "P$2") (pinfunction "P2_P$2") (pintype "bidirectional"))
      (node (ref "U$7") (pin "P$3") (pinfunction "P3_P$3") (pintype "bidirectional"))
    )
    (net (code "20") (name "IO3") (class "Default")
      (node (ref "IC1") (pin "15") (pinfunction "VDDTX_15") (pintype "input"))
      (node (ref "R21") (pin "2") (pinfunction "2_2") (pintype "passive"))
    )
    (net (code "21") (name "IO4") (class "Default")
      (node (ref "IC1") (pin "3") (pinfunction "CLKOUT_3") (pintype "output"))
      (node (ref "R25") (pin "2") (pinfunction "2_2") (pintype "passive"))
    )
    (net (code "22") (name "IO5") (class "Default")
      (node (ref "IC1") (pin "10") (pinfunction "~{RESET}_10") (pintype "input"))
      (node (ref "R24") (pin "2") (pinfunction "2_2") (pintype "passive"))
    )
    (net (code "23") (name "IO6") (class "Default")
      (node (ref "IC1") (pin "14") (pinfunction "RBIAS_14") (pintype "input"))
      (node (ref "R22") (pin "2") (pinfunction "2_2") (pintype "passive"))
    )
    (net (code "24") (name "IO7") (class "Default")
      (node (ref "IC1") (pin "16") (pinfunction "TPOUT-_16") (pintype "output"))
      (node (ref "R23") (pin "2") (pinfunction "2_2") (pintype "passive"))
    )
    (net (code "25") (name "IO8") (class "Default")
      (node (ref "IC1") (pin "17") (pinfunction "TPOUT+_17") (pintype "output"))
    )
    (net (code "26") (name "MCLR") (class "Default")
      (node (ref "C21") (pin "1") (pinfunction "1_1") (pintype "passive"))
      (node (ref "PROGRAMMING") (pin "7") (pinfunction "P$7_7") (pintype "power_in"))
      (node (ref "PROGRAMMING") (pin "8") (pinfunction "P$8_8") (pintype "power_in"))
      (node (ref "R13") (pin "2") (pinfunction "2_2") (pintype "passive"))
      (node (ref "R14") (pin "1") (pinfunction "1_1") (pintype "passive"))
      (node (ref "U$5") (pin "P$2") (pinfunction "P2_P$2") (pintype "bidirectional"))
      (node (ref "U$5") (pin "P$3") (pinfunction "P3_P$3") (pintype "bidirectional"))
    )
    (net (code "27") (name "MCLR'") (class "Default")
      (node (ref "R13") (pin "1") (pinfunction "1_1") (pintype "passive"))
    )
    (net (code "28") (name "Net-(C29-Pad1)") (class "Default")
      (node (ref "C29") (pin "1") (pinfunction "1_1") (pintype "passive"))
      (node (ref "R17") (pin "1") (pinfunction "1_1") (pintype "passive"))
      (node (ref "U$3") (pin "P9.5") (pinfunction "VDD_5V_P9.5") (pintype "bidirectional"))
      (node (ref "U$3") (pin "P9.6") (pinfunction "VDD_5V_P9.6") (pintype "bidirectional"))
    )
    (net (code "29") (name "Net-(D5-PadA)") (class "Default")
      (node (ref "D5") (pin "A") (pinfunction "A_A") (pintype "passive"))
      (node (ref "R15") (pin "2") (pinfunction "2_2") (pintype "passive"))
    )
    (net (code "30") (name "Net-(D6-PadA)") (class "Default")
      (node (ref "D6") (pin "A") (pinfunction "A_A") (pintype "passive"))
      (node (ref "R16") (pin "1") (pinfunction "1_1") (pintype "passive"))
    )
    (net (code "31") (name "Net-(LED1-PadA)") (class "Default")
      (node (ref "LED1") (pin "A") (pinfunction "A_A") (pintype "passive"))
      (node (ref "R6") (pin "1") (pinfunction "1_1") (pintype "passive"))
    )
    (net (code "32") (name "Net-(LED2-PadA)") (class "Default")
      (node (ref "LED2") (pin "A") (pinfunction "A_A") (pintype "passive"))
      (node (ref "R9") (pin "1") (pinfunction "1_1") (pintype "passive"))
    )
    (net (code "33") (name "Net-(LED3-PadA)") (class "Default")
      (node (ref "LED3") (pin "A") (pinfunction "A_A") (pintype "passive"))
      (node (ref "R12") (pin "1") (pinfunction "1_1") (pintype "passive"))
    )
    (net (code "34") (name "Net-(LED4-PadA)") (class "Default")
      (node (ref "LED4") (pin "A") (pinfunction "A_A") (pintype "passive"))
      (node (ref "R4") (pin "1") (pinfunction "1_1") (pintype "passive"))
    )
    (net (code "35") (name "Net-(LED5-PadA)") (class "Default")
      (node (ref "LED5") (pin "A") (pinfunction "A_A") (pintype "passive"))
      (node (ref "R21") (pin "1") (pinfunction "1_1") (pintype "passive"))
    )
    (net (code "36") (name "Net-(LED6-PadA)") (class "Default")
      (node (ref "LED6") (pin "A") (pinfunction "A_A") (pintype "passive"))
      (node (ref "R22") (pin "1") (pinfunction "1_1") (pintype "passive"))
    )
    (net (code "37") (name "Net-(LED7-PadA)") (class "Default")
      (node (ref "LED7") (pin "A") (pinfunction "A_A") (pintype "passive"))
      (node (ref "R23") (pin "1") (pinfunction "1_1") (pintype "passive"))
    )
    (net (code "38") (name "Net-(LED8-PadA)") (class "Default")
      (node (ref "LED8") (pin "A") (pinfunction "A_A") (pintype "passive"))
      (node (ref "R24") (pin "1") (pinfunction "1_1") (pintype "passive"))
    )
    (net (code "39") (name "Net-(LED9-PadA)") (class "Default")
      (node (ref "LED9") (pin "A") (pinfunction "A_A") (pintype "passive"))
      (node (ref "R25") (pin "1") (pinfunction "1_1") (pintype "passive"))
    )
    (net (code "40") (name "Net-(U$2-VSNS)") (class "Default")
      (node (ref "R2") (pin "1") (pinfunction "1_1") (pintype "passive"))
      (node (ref "R3") (pin "2") (pinfunction "2_2") (pintype "passive"))
      (node (ref "U$2") (pin "4") (pinfunction "VSNS_4") (pintype "passive"))
    )
    (net (code "41") (name "Net-(U$4-VSNS)") (class "Default")
      (node (ref "R1") (pin "1") (pinfunction "1_1") (pintype "passive"))
      (node (ref "R5") (pin "2") (pinfunction "2_2") (pintype "passive"))
      (node (ref "U$4") (pin "4") (pinfunction "VSNS_4") (pintype "passive"))
    )
    (net (code "42") (name "Net-(U$8-VSNS)") (class "Default")
      (node (ref "R7") (pin "1") (pinfunction "1_1") (pintype "passive"))
      (node (ref "R8") (pin "2") (pinfunction "2_2") (pintype "passive"))
      (node (ref "U$8") (pin "4") (pinfunction "VSNS_4") (pintype "passive"))
    )
    (net (code "43") (name "Net-(U$9-VSNS)") (class "Default")
      (node (ref "R10") (pin "1") (pinfunction "1_1") (pintype "passive"))
      (node (ref "R11") (pin "2") (pinfunction "2_2") (pintype "passive"))
      (node (ref "U$9") (pin "4") (pinfunction "VSNS_4") (pintype "passive"))
    )
    (net (code "44") (name "OC1") (class "Default")
      (node (ref "IC1") (pin "25") (pinfunction "VDDOSC_25") (pintype "input"))
      (node (ref "J2") (pin "1") (pinfunction "S_1") (pintype "passive"))
    )
    (net (code "45") (name "OC2") (class "Default")
      (node (ref "IC1") (pin "26") (pinfunction "LEDB_26") (pintype "output"))
      (node (ref "J1") (pin "1") (pinfunction "S_1") (pintype "passive"))
    )
    (net (code "46") (name "OC3") (class "Default")
      (node (ref "IC1") (pin "24") (pinfunction "OSC2_24") (pintype "output"))
      (node (ref "J3") (pin "1") (pinfunction "S_1") (pintype "passive"))
    )
    (net (code "47") (name "OC4") (class "Default")
      (node (ref "IC1") (pin "22") (pinfunction "VSSOSC_22") (pintype "input"))
      (node (ref "J4") (pin "1") (pinfunction "S_1") (pintype "passive"))
    )
    (net (code "48") (name "OC5") (class "Default")
      (node (ref "IC1") (pin "21") (pinfunction "VSSPLL_21") (pintype "input"))
      (node (ref "J5") (pin "1") (pinfunction "S_1") (pintype "passive"))
    )
    (net (code "49") (name "OC6") (class "Default")
      (node (ref "IC1") (pin "18") (pinfunction "VSSTX_18") (pintype "input"))
      (node (ref "J6") (pin "1") (pinfunction "S_1") (pintype "passive"))
    )
    (net (code "50") (name "PGC1") (class "Default")
      (node (ref "IC1") (pin "5") (pinfunction "NC*_5") (pintype "output"))
      (node (ref "PROGRAMMING") (pin "3") (pinfunction "P$3_3") (pintype "power_in"))
      (node (ref "PROGRAMMING") (pin "4") (pinfunction "P$4_4") (pintype "power_in"))
    )
    (net (code "51") (name "PGD1") (class "Default")
      (node (ref "IC1") (pin "4") (pinfunction "~{INT}_4") (pintype "output"))
      (node (ref "PROGRAMMING") (pin "5") (pinfunction "P$5_5") (pintype "power_in"))
      (node (ref "PROGRAMMING") (pin "6") (pinfunction "P$6_6") (pintype "power_in"))
    )
    (net (code "52") (name "PH1") (class "Default")
      (node (ref "C4") (pin "2") (pinfunction "2_2") (pintype "passive"))
      (node (ref "D2") (pin "3") (pinfunction "K_3") (pintype "passive"))
      (node (ref "L1") (pin "1") (pinfunction "1_1") (pintype "passive"))
      (node (ref "U$2") (pin "8") (pinfunction "PH_8") (pintype "passive"))
    )
    (net (code "53") (name "PH2") (class "Default")
      (node (ref "C3") (pin "2") (pinfunction "2_2") (pintype "passive"))
      (node (ref "D1") (pin "3") (pinfunction "K_3") (pintype "passive"))
      (node (ref "L2") (pin "1") (pinfunction "1_1") (pintype "passive"))
      (node (ref "U$4") (pin "8") (pinfunction "PH_8") (pintype "passive"))
    )
    (net (code "54") (name "PH3") (class "Default")
      (node (ref "C14") (pin "2") (pinfunction "2_2") (pintype "passive"))
      (node (ref "D3") (pin "3") (pinfunction "K_3") (pintype "passive"))
      (node (ref "L3") (pin "1") (pinfunction "1_1") (pintype "passive"))
      (node (ref "U$8") (pin "8") (pinfunction "PH_8") (pintype "passive"))
    )
    (net (code "55") (name "PH4") (class "Default")
      (node (ref "C20") (pin "2") (pinfunction "2_2") (pintype "passive"))
      (node (ref "D4") (pin "3") (pinfunction "K_3") (pintype "passive"))
      (node (ref "L4") (pin "1") (pinfunction "1_1") (pintype "passive"))
      (node (ref "U$9") (pin "8") (pinfunction "PH_8") (pintype "passive"))
    )
    (net (code "56") (name "SCL") (class "Default")
      (node (ref "IC1") (pin "7") (pinfunction "SI_7") (pintype "input"))
      (node (ref "U$1") (pin "P9.19") (pinfunction "I2C2_SCL_P9.19") (pintype "bidirectional"))
    )
    (net (code "57") (name "SDA") (class "Default")
      (node (ref "IC1") (pin "6") (pinfunction "SO_6") (pintype "output"))
      (node (ref "U$1") (pin "P9.20") (pinfunction "I2C2_SDA_P9.20") (pintype "bidirectional"))
    )
    (net (code "58") (name "VCC") (class "Default")
      (node (ref "C1") (pin "2") (pinfunction "2_2") (pintype "passive"))
      (node (ref "C10") (pin "2") (pinfunction "2_2") (pintype "passive"))
      (node (ref "C11") (pin "2") (pinfunction "2_2") (pintype "passive"))
      (node (ref "C12") (pin "2") (pinfunction "2_2") (pintype "passive"))
      (node (ref "C13") (pin "2") (pinfunction "2_2") (pintype "passive"))
      (node (ref "C16") (pin "2") (pinfunction "2_2") (pintype "passive"))
      (node (ref "C17") (pin "2") (pinfunction "2_2") (pintype "passive"))
      (node (ref "C18") (pin "2") (pinfunction "2_2") (pintype "passive"))
      (node (ref "C19") (pin "2") (pinfunction "2_2") (pintype "passive"))
      (node (ref "C2") (pin "2") (pinfunction "2_2") (pintype "passive"))
      (node (ref "C30") (pin "2") (pinfunction "2_2") (pintype "passive"))
      (node (ref "C31") (pin "2") (pinfunction "2_2") (pintype "passive"))
      (node (ref "C32") (pin "2") (pinfunction "2_2") (pintype "passive"))
      (node (ref "C6") (pin "2") (pinfunction "2_2") (pintype "passive"))
      (node (ref "C7") (pin "2") (pinfunction "2_2") (pintype "passive"))
      (node (ref "C8") (pin "2") (pinfunction "2_2") (pintype "passive"))
      (node (ref "U$2") (pin "7") (pinfunction "VIN_7") (pintype "passive"))
      (node (ref "U$4") (pin "7") (pinfunction "VIN_7") (pintype "passive"))
      (node (ref "U$8") (pin "7") (pinfunction "VIN_7") (pintype "passive"))
      (node (ref "U$9") (pin "7") (pinfunction "VIN_7") (pintype "passive"))
    )
    (net (code "59") (name "VOUT1") (class "Default")
      (node (ref "C5") (pin "1") (pinfunction "+_1") (pintype "passive"))
      (node (ref "L1") (pin "2") (pinfunction "2_2") (pintype "passive"))
      (node (ref "R2") (pin "2") (pinfunction "2_2") (pintype "passive"))
      (node (ref "R4") (pin "2") (pinfunction "2_2") (pintype "passive"))
    )
    (net (code "60") (name "VOUT2") (class "Default")
      (node (ref "C9") (pin "1") (pinfunction "+_1") (pintype "passive"))
      (node (ref "L2") (pin "2") (pinfunction "2_2") (pintype "passive"))
      (node (ref "R1") (pin "2") (pinfunction "2_2") (pintype "passive"))
      (node (ref "R6") (pin "2") (pinfunction "2_2") (pintype "passive"))
    )
    (net (code "61") (name "VOUT3") (class "Default")
      (node (ref "C15") (pin "1") (pinfunction "+_1") (pintype "passive"))
      (node (ref "L3") (pin "2") (pinfunction "2_2") (pintype "passive"))
      (node (ref "R7") (pin "2") (pinfunction "2_2") (pintype "passive"))
      (node (ref "R9") (pin "2") (pinfunction "2_2") (pintype "passive"))
    )
    (net (code "62") (name "VOUT4") (class "Default")
      (node (ref "C22") (pin "1") (pinfunction "+_1") (pintype "passive"))
      (node (ref "L4") (pin "2") (pinfunction "2_2") (pintype "passive"))
      (node (ref "R10") (pin "2") (pinfunction "2_2") (pintype "passive"))
      (node (ref "R12") (pin "2") (pinfunction "2_2") (pintype "passive"))
    )
    (net (code "63") (name "VSS") (class "Default")
      (node (ref "C21") (pin "2") (pinfunction "2_2") (pintype "passive"))
      (node (ref "C23") (pin "C") (pinfunction "-_C") (pintype "passive"))
      (node (ref "C24") (pin "C") (pinfunction "-_C") (pintype "passive"))
      (node (ref "C25") (pin "2") (pinfunction "2_2") (pintype "passive"))
      (node (ref "C26") (pin "2") (pinfunction "2_2") (pintype "passive"))
      (node (ref "C27") (pin "2") (pinfunction "2_2") (pintype "passive"))
      (node (ref "C28") (pin "2") (pinfunction "2_2") (pintype "passive"))
      (node (ref "D5") (pin "C") (pinfunction "C_C") (pintype "passive"))
      (node (ref "D6") (pin "C") (pinfunction "C_C") (pintype "passive"))
      (node (ref "IC1") (pin "27") (pinfunction "LEDA_27") (pintype "output"))
      (node (ref "IC1") (pin "8") (pinfunction "SCK_8") (pintype "input"))
      (node (ref "J1") (pin "3") (pinfunction "S_3") (pintype "passive"))
      (node (ref "J2") (pin "3") (pinfunction "S_3") (pintype "passive"))
      (node (ref "J3") (pin "3") (pinfunction "S_3") (pintype "passive"))
      (node (ref "J4") (pin "3") (pinfunction "S_3") (pintype "passive"))
      (node (ref "J5") (pin "3") (pinfunction "S_3") (pintype "passive"))
      (node (ref "J6") (pin "3") (pinfunction "S_3") (pintype "passive"))
      (node (ref "LED5") (pin "C") (pinfunction "C_C") (pintype "passive"))
      (node (ref "LED6") (pin "C") (pinfunction "C_C") (pintype "passive"))
      (node (ref "LED7") (pin "C") (pinfunction "C_C") (pintype "passive"))
      (node (ref "LED8") (pin "C") (pinfunction "C_C") (pintype "passive"))
      (node (ref "LED9") (pin "C") (pinfunction "C_C") (pintype "passive"))
      (node (ref "PROGRAMMING") (pin "10") (pinfunction "P$10_10") (pintype "power_in"))
      (node (ref "PROGRAMMING") (pin "9") (pinfunction "P$9_9") (pintype "power_in"))
      (node (ref "R19") (pin "2") (pinfunction "2_2") (pintype "passive"))
      (node (ref "R20") (pin "2") (pinfunction "2_2") (pintype "passive"))
      (node (ref "U$5") (pin "P$1") (pinfunction "P1_P$1") (pintype "bidirectional"))
      (node (ref "U$5") (pin "P$4") (pinfunction "P4_P$4") (pintype "bidirectional"))
      (node (ref "U3") (pin "1") (pinfunction "GND_1") (pintype "passive"))
    )
    (net (code "64") (name "unconnected-(H1-MOUNT-PadB3,0)") (class "Default")
      (node (ref "H1") (pin "B3,0") (pinfunction "MOUNT_B3,0") (pintype "passive"))
    )
    (net (code "65") (name "unconnected-(H2-MOUNT-PadB3,0)") (class "Default")
      (node (ref "H2") (pin "B3,0") (pinfunction "MOUNT_B3,0") (pintype "passive"))
    )
    (net (code "66") (name "unconnected-(H3-MOUNT-PadB3,0)") (class "Default")
      (node (ref "H3") (pin "B3,0") (pinfunction "MOUNT_B3,0") (pintype "passive"))
    )
    (net (code "67") (name "unconnected-(H4-MOUNT-PadB3,0)") (class "Default")
      (node (ref "H4") (pin "B3,0") (pinfunction "MOUNT_B3,0") (pintype "passive"))
    )
    (net (code "68") (name "unconnected-(IC1-OSC1-Pad23)") (class "Default")
      (node (ref "IC1") (pin "23") (pinfunction "OSC1_23") (pintype "input"))
    )
    (net (code "69") (name "unconnected-(IC1-TPIN--Pad12)") (class "Default")
      (node (ref "IC1") (pin "12") (pinfunction "TPIN-_12") (pintype "input"))
    )
    (net (code "70") (name "unconnected-(IC1-VCAP-Pad1)") (class "Default")
      (node (ref "IC1") (pin "1") (pinfunction "VCAP_1") (pintype "input"))
    )
    (net (code "71") (name "unconnected-(IC1-VDDPLL-Pad20)") (class "Default")
      (node (ref "IC1") (pin "20") (pinfunction "VDDPLL_20") (pintype "input"))
    )
    (net (code "72") (name "unconnected-(IC1-VDDRX-Pad19)") (class "Default")
      (node (ref "IC1") (pin "19") (pinfunction "VDDRX_19") (pintype "input"))
    )
    (net (code "73") (name "unconnected-(IC1-VSSRX-Pad11)") (class "Default")
      (node (ref "IC1") (pin "11") (pinfunction "VSSRX_11") (pintype "input"))
    )
    (net (code "74") (name "unconnected-(IC2-OSC1{slash}CLKI{slash}RA7-Pad9)") (class "Default")
      (node (ref "IC2") (pin "9") (pinfunction "OSC1/CLKI/RA7_9") (pintype "bidirectional"))
    )
    (net (code "75") (name "unconnected-(IC2-OSC2{slash}CLKO{slash}RA6-Pad10)") (class "Default")
      (node (ref "IC2") (pin "10") (pinfunction "OSC2/CLKO/RA6_10") (pintype "bidirectional"))
    )
    (net (code "76") (name "unconnected-(IC2-RA0{slash}AN0{slash}C1INA{slash}ULPWU{slash}RP0-Pad2)") (class "Default")
      (node (ref "IC2") (pin "2") (pinfunction "RA0/AN0/C1INA/ULPWU/RP0_2") (pintype "bidirectional"))
    )
    (net (code "77") (name "unconnected-(IC2-RA1{slash}AN1{slash}C2INA{slash}VBG{slash}RP1-Pad3)") (class "Default")
      (node (ref "IC2") (pin "3") (pinfunction "RA1/AN1/C2INA/VBG/RP1_3") (pintype "bidirectional"))
    )
    (net (code "78") (name "unconnected-(IC2-RA2{slash}AN2{slash}C2INB{slash}C1IND{slash}C3INB{slash}VREF-{slash}CVREF-Pad4)") (class "Default")
      (node (ref "IC2") (pin "4") (pinfunction "RA2/AN2/C2INB/C1IND/C3INB/VREF-/CVREF_4") (pintype "bidirectional"))
    )
    (net (code "79") (name "unconnected-(IC2-RA3{slash}AN3{slash}C1INB{slash}VREF+-Pad5)") (class "Default")
      (node (ref "IC2") (pin "5") (pinfunction "RA3/AN3/C1INB/VREF+_5") (pintype "bidirectional"))
    )
    (net (code "80") (name "unconnected-(IC2-RA5{slash}AN4{slash}C1INC{slash}~{SS1}{slash}HLVDIN{slash}RCV{slash}RP2-Pad7)") (class "Default")
      (node (ref "IC2") (pin "7") (pinfunction "RA5/AN4/C1INC/~{SS1}/HLVDIN/RCV/RP2_7") (pintype "bidirectional"))
    )
    (net (code "81") (name "unconnected-(IC2-RB0{slash}AN12{slash}C3IND{slash}INT0{slash}RP3-Pad21)") (class "Default")
      (node (ref "IC2") (pin "21") (pinfunction "RB0/AN12/C3IND/INT0/RP3_21") (pintype "bidirectional"))
    )
    (net (code "82") (name "unconnected-(IC2-RB1{slash}AN10{slash}C3INC{slash}RTCC{slash}RP4-Pad22)") (class "Default")
      (node (ref "IC2") (pin "22") (pinfunction "RB1/AN10/C3INC/RTCC/RP4_22") (pintype "bidirectional"))
    )
    (net (code "83") (name "unconnected-(IC2-RB2{slash}AN8{slash}C2INC{slash}CTED1{slash}VMO{slash}REFO{slash}RP5-Pad23)") (class "Default")
      (node (ref "IC2") (pin "23") (pinfunction "RB2/AN8/C2INC/CTED1/VMO/REFO/RP5_23") (pintype "bidirectional"))
    )
    (net (code "84") (name "unconnected-(IC2-RB3{slash}AN9{slash}C3INA{slash}CTED2{slash}VPO{slash}RP6-Pad24)") (class "Default")
      (node (ref "IC2") (pin "24") (pinfunction "RB3/AN9/C3INA/CTED2/VPO/RP6_24") (pintype "bidirectional"))
    )
    (net (code "85") (name "unconnected-(IC2-RB4{slash}CCP4{slash}KBI0{slash}SCK1{slash}SCL1{slash}RP7-Pad25)") (class "Default")
      (node (ref "IC2") (pin "25") (pinfunction "RB4/CCP4/KBI0/SCK1/SCL1/RP7_25") (pintype "bidirectional"))
    )
    (net (code "86") (name "unconnected-(IC2-RB5{slash}CCP5{slash}KBI1{slash}SDI1{slash}SDA1{slash}RP8-Pad26)") (class "Default")
      (node (ref "IC2") (pin "26") (pinfunction "RB5/CCP5/KBI1/SDI1/SDA1/RP8_26") (pintype "bidirectional"))
    )
    (net (code "87") (name "unconnected-(IC2-RB6{slash}CCP6{slash}KBI2{slash}PGC{slash}RP9-Pad27)") (class "Default")
      (node (ref "IC2") (pin "27") (pinfunction "RB6/CCP6/KBI2/PGC/RP9_27") (pintype "bidirectional"))
    )
    (net (code "88") (name "unconnected-(IC2-RB7{slash}CCP7{slash}KBI3{slash}PGD{slash}RP10-Pad28)") (class "Default")
      (node (ref "IC2") (pin "28") (pinfunction "RB7/CCP7/KBI3/PGD/RP10_28") (pintype "bidirectional"))
    )
    (net (code "89") (name "unconnected-(IC2-RC0{slash}T1OSO{slash}T1CKI{slash}RP11-Pad11)") (class "Default")
      (node (ref "IC2") (pin "11") (pinfunction "RC0/T1OSO/T1CKI/RP11_11") (pintype "bidirectional"))
    )
    (net (code "90") (name "unconnected-(IC2-RC1{slash}CCP8{slash}T1OSI{slash}~{UOE}{slash}RP12-Pad12)") (class "Default")
      (node (ref "IC2") (pin "12") (pinfunction "RC1/CCP8/T1OSI/~{UOE}/RP12_12") (pintype "bidirectional"))
    )
    (net (code "91") (name "unconnected-(IC2-RC2{slash}AN11{slash}C2IND{slash}CTPLS{slash}RP13-Pad13)") (class "Default")
      (node (ref "IC2") (pin "13") (pinfunction "RC2/AN11/C2IND/CTPLS/RP13_13") (pintype "bidirectional"))
    )
    (net (code "92") (name "unconnected-(IC2-RC4{slash}D-{slash}VM-Pad15)") (class "Default")
      (node (ref "IC2") (pin "15") (pinfunction "RC4/D-/VM_15") (pintype "bidirectional"))
    )
    (net (code "93") (name "unconnected-(IC2-RC5{slash}D+{slash}VP-Pad16)") (class "Default")
      (node (ref "IC2") (pin "16") (pinfunction "RC5/D+/VP_16") (pintype "bidirectional"))
    )
    (net (code "94") (name "unconnected-(IC2-RC6{slash}CCP9{slash}TX1{slash}CK1{slash}RP17-Pad17)") (class "Default")
      (node (ref "IC2") (pin "17") (pinfunction "RC6/CCP9/TX1/CK1/RP17_17") (pintype "bidirectional"))
    )
    (net (code "95") (name "unconnected-(IC2-RC7{slash}CCP10{slash}RX1{slash}DT1{slash}SDO1{slash}RP18-Pad18)") (class "Default")
      (node (ref "IC2") (pin "18") (pinfunction "RC7/CCP10/RX1/DT1/SDO1/RP18_18") (pintype "bidirectional"))
    )
    (net (code "96") (name "unconnected-(IC2-VDD-Pad20)") (class "Default")
      (node (ref "IC2") (pin "20") (pinfunction "VDD_20") (pintype "input"))
    )
    (net (code "97") (name "unconnected-(IC2-VDDCORE{slash}VCAP-Pad6)") (class "Default")
      (node (ref "IC2") (pin "6") (pinfunction "VDDCORE/VCAP_6") (pintype "input"))
    )
    (net (code "98") (name "unconnected-(IC2-VSS1-Pad8)") (class "Default")
      (node (ref "IC2") (pin "8") (pinfunction "VSS1_8") (pintype "input"))
    )
    (net (code "99") (name "unconnected-(IC2-VSS2-Pad19)") (class "Default")
      (node (ref "IC2") (pin "19") (pinfunction "VSS2_19") (pintype "input"))
    )
    (net (code "100") (name "unconnected-(IC2-VUSB-Pad14)") (class "Default")
      (node (ref "IC2") (pin "14") (pinfunction "VUSB_14") (pintype "input"))
    )
    (net (code "101") (name "unconnected-(IC2-~{MCLR}-Pad1)") (class "Default")
      (node (ref "IC2") (pin "1") (pinfunction "~{MCLR}_1") (pintype "input"))
    )
    (net (code "102") (name "unconnected-(U$1A-GPIO_8-PadP8.35)") (class "Default")
      (node (ref "U$1") (pin "P8.35") (pinfunction "GPIO_8_P8.35") (pintype "bidirectional"))
    )
    (net (code "103") (name "unconnected-(U$1A-GPIO_9-PadP8.33)") (class "Default")
      (node (ref "U$1") (pin "P8.33") (pinfunction "GPIO_9_P8.33") (pintype "bidirectional"))
    )
    (net (code "104") (name "unconnected-(U$1A-GPIO_10-PadP8.31)") (class "Default")
      (node (ref "U$1") (pin "P8.31") (pinfunction "GPIO_10_P8.31") (pintype "bidirectional"))
    )
    (net (code "105") (name "unconnected-(U$1A-GPIO_11-PadP8.32)") (class "Default")
      (node (ref "U$1") (pin "P8.32") (pinfunction "GPIO_11_P8.32") (pintype "bidirectional"))
    )
    (net (code "106") (name "unconnected-(U$1A-GPIO_22-PadP8.19)") (class "Default")
      (node (ref "U$1") (pin "P8.19") (pinfunction "GPIO_22_P8.19") (pintype "bidirectional"))
    )
    (net (code "107") (name "unconnected-(U$1A-GPIO_23-PadP8.13)") (class "Default")
      (node (ref "U$1") (pin "P8.13") (pinfunction "GPIO_23_P8.13") (pintype "bidirectional"))
    )
    (net (code "108") (name "unconnected-(U$1A-GPIO_26-PadP8.14)") (class "Default")
      (node (ref "U$1") (pin "P8.14") (pinfunction "GPIO_26_P8.14") (pintype "bidirectional"))
    )
    (net (code "109") (name "unconnected-(U$1A-GPIO_27-PadP8.17)") (class "Default")
      (node (ref "U$1") (pin "P8.17") (pinfunction "GPIO_27_P8.17") (pintype "bidirectional"))
    )
    (net (code "110") (name "unconnected-(U$1A-GPIO_32-PadP8.25)") (class "Default")
      (node (ref "U$1") (pin "P8.25") (pinfunction "GPIO_32_P8.25") (pintype "bidirectional"))
    )
    (net (code "111") (name "unconnected-(U$1A-GPIO_33-PadP8.24)") (class "Default")
      (node (ref "U$1") (pin "P8.24") (pinfunction "GPIO_33_P8.24") (pintype "bidirectional"))
    )
    (net (code "112") (name "unconnected-(U$1A-GPIO_34-PadP8.5)") (class "Default")
      (node (ref "U$1") (pin "P8.5") (pinfunction "GPIO_34_P8.5") (pintype "bidirectional"))
    )
    (net (code "113") (name "unconnected-(U$1A-GPIO_35-PadP8.6)") (class "Default")
      (node (ref "U$1") (pin "P8.6") (pinfunction "GPIO_35_P8.6") (pintype "bidirectional"))
    )
    (net (code "114") (name "unconnected-(U$1A-GPIO_36-PadP8.23)") (class "Default")
      (node (ref "U$1") (pin "P8.23") (pinfunction "GPIO_36_P8.23") (pintype "bidirectional"))
    )
    (net (code "115") (name "unconnected-(U$1A-GPIO_37-PadP8.22)") (class "Default")
      (node (ref "U$1") (pin "P8.22") (pinfunction "GPIO_37_P8.22") (pintype "bidirectional"))
    )
    (net (code "116") (name "unconnected-(U$1A-GPIO_38-PadP8.3)") (class "Default")
      (node (ref "U$1") (pin "P8.3") (pinfunction "GPIO_38_P8.3") (pintype "bidirectional"))
    )
    (net (code "117") (name "unconnected-(U$1A-GPIO_39-PadP8.4)") (class "Default")
      (node (ref "U$1") (pin "P8.4") (pinfunction "GPIO_39_P8.4") (pintype "bidirectional"))
    )
    (net (code "118") (name "unconnected-(U$1A-GPIO_44-PadP8.12)") (class "Default")
      (node (ref "U$1") (pin "P8.12") (pinfunction "GPIO_44_P8.12") (pintype "bidirectional"))
    )
    (net (code "119") (name "unconnected-(U$1A-GPIO_45-PadP8.11)") (class "Default")
      (node (ref "U$1") (pin "P8.11") (pinfunction "GPIO_45_P8.11") (pintype "bidirectional"))
    )
    (net (code "120") (name "unconnected-(U$1A-GPIO_46-PadP8.16)") (class "Default")
      (node (ref "U$1") (pin "P8.16") (pinfunction "GPIO_46_P8.16") (pintype "bidirectional"))
    )
    (net (code "121") (name "unconnected-(U$1A-GPIO_47-PadP8.15)") (class "Default")
      (node (ref "U$1") (pin "P8.15") (pinfunction "GPIO_47_P8.15") (pintype "bidirectional"))
    )
    (net (code "122") (name "unconnected-(U$1A-GPIO_61-PadP8.26)") (class "Default")
      (node (ref "U$1") (pin "P8.26") (pinfunction "GPIO_61_P8.26") (pintype "bidirectional"))
    )
    (net (code "123") (name "unconnected-(U$1A-GPIO_62-PadP8.21)") (class "Default")
      (node (ref "U$1") (pin "P8.21") (pinfunction "GPIO_62_P8.21") (pintype "bidirectional"))
    )
    (net (code "124") (name "unconnected-(U$1A-GPIO_63-PadP8.20)") (class "Default")
      (node (ref "U$1") (pin "P8.20") (pinfunction "GPIO_63_P8.20") (pintype "bidirectional"))
    )
    (net (code "125") (name "unconnected-(U$1A-GPIO_65-PadP8.18)") (class "Default")
      (node (ref "U$1") (pin "P8.18") (pinfunction "GPIO_65_P8.18") (pintype "bidirectional"))
    )
    (net (code "126") (name "unconnected-(U$1A-GPIO_66-PadP8.7)") (class "Default")
      (node (ref "U$1") (pin "P8.7") (pinfunction "GPIO_66_P8.7") (pintype "bidirectional"))
    )
    (net (code "127") (name "unconnected-(U$1A-GPIO_67-PadP8.8)") (class "Default")
      (node (ref "U$1") (pin "P8.8") (pinfunction "GPIO_67_P8.8") (pintype "bidirectional"))
    )
    (net (code "128") (name "unconnected-(U$1A-GPIO_68-PadP8.10)") (class "Default")
      (node (ref "U$1") (pin "P8.10") (pinfunction "GPIO_68_P8.10") (pintype "bidirectional"))
    )
    (net (code "129") (name "unconnected-(U$1A-GPIO_69-PadP8.9)") (class "Default")
      (node (ref "U$1") (pin "P8.9") (pinfunction "GPIO_69_P8.9") (pintype "bidirectional"))
    )
    (net (code "130") (name "unconnected-(U$1A-GPIO_70-PadP8.45)") (class "Default")
      (node (ref "U$1") (pin "P8.45") (pinfunction "GPIO_70_P8.45") (pintype "bidirectional"))
    )
    (net (code "131") (name "unconnected-(U$1A-GPIO_71-PadP8.46)") (class "Default")
      (node (ref "U$1") (pin "P8.46") (pinfunction "GPIO_71_P8.46") (pintype "bidirectional"))
    )
    (net (code "132") (name "unconnected-(U$1A-GPIO_72-PadP8.43)") (class "Default")
      (node (ref "U$1") (pin "P8.43") (pinfunction "GPIO_72_P8.43") (pintype "bidirectional"))
    )
    (net (code "133") (name "unconnected-(U$1A-GPIO_73-PadP8.44)") (class "Default")
      (node (ref "U$1") (pin "P8.44") (pinfunction "GPIO_73_P8.44") (pintype "bidirectional"))
    )
    (net (code "134") (name "unconnected-(U$1A-GPIO_74-PadP8.41)") (class "Default")
      (node (ref "U$1") (pin "P8.41") (pinfunction "GPIO_74_P8.41") (pintype "bidirectional"))
    )
    (net (code "135") (name "unconnected-(U$1A-GPIO_75-PadP8.42)") (class "Default")
      (node (ref "U$1") (pin "P8.42") (pinfunction "GPIO_75_P8.42") (pintype "bidirectional"))
    )
    (net (code "136") (name "unconnected-(U$1A-GPIO_76-PadP8.39)") (class "Default")
      (node (ref "U$1") (pin "P8.39") (pinfunction "GPIO_76_P8.39") (pintype "bidirectional"))
    )
    (net (code "137") (name "unconnected-(U$1A-GPIO_77-PadP8.40)") (class "Default")
      (node (ref "U$1") (pin "P8.40") (pinfunction "GPIO_77_P8.40") (pintype "bidirectional"))
    )
    (net (code "138") (name "unconnected-(U$1A-GPIO_78-PadP8.37)") (class "Default")
      (node (ref "U$1") (pin "P8.37") (pinfunction "GPIO_78_P8.37") (pintype "bidirectional"))
    )
    (net (code "139") (name "unconnected-(U$1A-GPIO_79-PadP8.38)") (class "Default")
      (node (ref "U$1") (pin "P8.38") (pinfunction "GPIO_79_P8.38") (pintype "bidirectional"))
    )
    (net (code "140") (name "unconnected-(U$1A-GPIO_80-PadP8.36)") (class "Default")
      (node (ref "U$1") (pin "P8.36") (pinfunction "GPIO_80_P8.36") (pintype "bidirectional"))
    )
    (net (code "141") (name "unconnected-(U$1A-GPIO_81-PadP8.34)") (class "Default")
      (node (ref "U$1") (pin "P8.34") (pinfunction "GPIO_81_P8.34") (pintype "bidirectional"))
    )
    (net (code "142") (name "unconnected-(U$1A-GPIO_86-PadP8.27)") (class "Default")
      (node (ref "U$1") (pin "P8.27") (pinfunction "GPIO_86_P8.27") (pintype "bidirectional"))
    )
    (net (code "143") (name "unconnected-(U$1A-GPIO_87-PadP8.29)") (class "Default")
      (node (ref "U$1") (pin "P8.29") (pinfunction "GPIO_87_P8.29") (pintype "bidirectional"))
    )
    (net (code "144") (name "unconnected-(U$1A-GPIO_88-PadP8.28)") (class "Default")
      (node (ref "U$1") (pin "P8.28") (pinfunction "GPIO_88_P8.28") (pintype "bidirectional"))
    )
    (net (code "145") (name "unconnected-(U$1A-GPIO_89-PadP8.30)") (class "Default")
      (node (ref "U$1") (pin "P8.30") (pinfunction "GPIO_89_P8.30") (pintype "bidirectional"))
    )
    (net (code "146") (name "unconnected-(U$1B-AIN0-PadP9.39)") (class "Default")
      (node (ref "U$1") (pin "P9.39") (pinfunction "AIN0_P9.39") (pintype "bidirectional"))
    )
    (net (code "147") (name "unconnected-(U$1B-AIN1-PadP9.40)") (class "Default")
      (node (ref "U$1") (pin "P9.40") (pinfunction "AIN1_P9.40") (pintype "bidirectional"))
    )
    (net (code "148") (name "unconnected-(U$1B-AIN2-PadP9.37)") (class "Default")
      (node (ref "U$1") (pin "P9.37") (pinfunction "AIN2_P9.37") (pintype "bidirectional"))
    )
    (net (code "149") (name "unconnected-(U$1B-AIN3-PadP9.38)") (class "Default")
      (node (ref "U$1") (pin "P9.38") (pinfunction "AIN3_P9.38") (pintype "bidirectional"))
    )
    (net (code "150") (name "unconnected-(U$1B-AIN4-PadP9.33)") (class "Default")
      (node (ref "U$1") (pin "P9.33") (pinfunction "AIN4_P9.33") (pintype "bidirectional"))
    )
    (net (code "151") (name "unconnected-(U$1B-AIN5-PadP9.36)") (class "Default")
      (node (ref "U$1") (pin "P9.36") (pinfunction "AIN5_P9.36") (pintype "bidirectional"))
    )
    (net (code "152") (name "unconnected-(U$1B-AIN6-PadP9.35)") (class "Default")
      (node (ref "U$1") (pin "P9.35") (pinfunction "AIN6_P9.35") (pintype "bidirectional"))
    )
    (net (code "153") (name "unconnected-(U$1B-GNDA_ADC-PadP9.34)") (class "Default")
      (node (ref "U$1") (pin "P9.34") (pinfunction "GNDA_ADC_P9.34") (pintype "bidirectional"))
    )
    (net (code "154") (name "unconnected-(U$1B-GPIO_2-PadP9.22)") (class "Default")
      (node (ref "U$1") (pin "P9.22") (pinfunction "GPIO_2_P9.22") (pintype "bidirectional"))
    )
    (net (code "155") (name "unconnected-(U$1B-GPIO_3-PadP9.21)") (class "Default")
      (node (ref "U$1") (pin "P9.21") (pinfunction "GPIO_3_P9.21") (pintype "bidirectional"))
    )
    (net (code "156") (name "unconnected-(U$1B-GPIO_4-PadP9.17)") (class "Default")
      (node (ref "U$1") (pin "P9.17") (pinfunction "GPIO_4_P9.17") (pintype "bidirectional"))
    )
    (net (code "157") (name "unconnected-(U$1B-GPIO_5-PadP9.18)") (class "Default")
      (node (ref "U$1") (pin "P9.18") (pinfunction "GPIO_5_P9.18") (pintype "bidirectional"))
    )
    (net (code "158") (name "unconnected-(U$1B-GPIO_7-PadP9.42)") (class "Default")
      (node (ref "U$1") (pin "P9.42") (pinfunction "GPIO_7_P9.42") (pintype "bidirectional"))
    )
    (net (code "159") (name "unconnected-(U$1B-GPIO_14-PadP9.26)") (class "Default")
      (node (ref "U$1") (pin "P9.26") (pinfunction "GPIO_14_P9.26") (pintype "bidirectional"))
    )
    (net (code "160") (name "unconnected-(U$1B-GPIO_15-PadP9.24)") (class "Default")
      (node (ref "U$1") (pin "P9.24") (pinfunction "GPIO_15_P9.24") (pintype "bidirectional"))
    )
    (net (code "161") (name "unconnected-(U$1B-GPIO_20-PadP9.41)") (class "Default")
      (node (ref "U$1") (pin "P9.41") (pinfunction "GPIO_20_P9.41") (pintype "bidirectional"))
    )
    (net (code "162") (name "unconnected-(U$1B-GPIO_30-PadP9.11)") (class "Default")
      (node (ref "U$1") (pin "P9.11") (pinfunction "GPIO_30_P9.11") (pintype "bidirectional"))
    )
    (net (code "163") (name "unconnected-(U$1B-GPIO_31-PadP9.13)") (class "Default")
      (node (ref "U$1") (pin "P9.13") (pinfunction "GPIO_31_P9.13") (pintype "bidirectional"))
    )
    (net (code "164") (name "unconnected-(U$1B-GPIO_40-PadP9.14)") (class "Default")
      (node (ref "U$1") (pin "P9.14") (pinfunction "GPIO_40_P9.14") (pintype "bidirectional"))
    )
    (net (code "165") (name "unconnected-(U$1B-GPIO_48-PadP9.15)") (class "Default")
      (node (ref "U$1") (pin "P9.15") (pinfunction "GPIO_48_P9.15") (pintype "bidirectional"))
    )
    (net (code "166") (name "unconnected-(U$1B-GPIO_49-PadP9.23)") (class "Default")
      (node (ref "U$1") (pin "P9.23") (pinfunction "GPIO_49_P9.23") (pintype "bidirectional"))
    )
    (net (code "167") (name "unconnected-(U$1B-GPIO_51-PadP9.16)") (class "Default")
      (node (ref "U$1") (pin "P9.16") (pinfunction "GPIO_51_P9.16") (pintype "bidirectional"))
    )
    (net (code "168") (name "unconnected-(U$1B-GPIO_60-PadP9.12)") (class "Default")
      (node (ref "U$1") (pin "P9.12") (pinfunction "GPIO_60_P9.12") (pintype "bidirectional"))
    )
    (net (code "169") (name "unconnected-(U$1B-GPIO_117-PadP9.25)") (class "Default")
      (node (ref "U$1") (pin "P9.25") (pinfunction "GPIO_117_P9.25") (pintype "bidirectional"))
    )
    (net (code "170") (name "unconnected-(U$1B-GPIO_120-PadP9.31)") (class "Default")
      (node (ref "U$1") (pin "P9.31") (pinfunction "GPIO_120_P9.31") (pintype "bidirectional"))
    )
    (net (code "171") (name "unconnected-(U$1B-GPIO_121-PadP9.29)") (class "Default")
      (node (ref "U$1") (pin "P9.29") (pinfunction "GPIO_121_P9.29") (pintype "bidirectional"))
    )
    (net (code "172") (name "unconnected-(U$1B-GPIO_122-PadP9.30)") (class "Default")
      (node (ref "U$1") (pin "P9.30") (pinfunction "GPIO_122_P9.30") (pintype "bidirectional"))
    )
    (net (code "173") (name "unconnected-(U$1B-GPIO_123-PadP9.28)") (class "Default")
      (node (ref "U$1") (pin "P9.28") (pinfunction "GPIO_123_P9.28") (pintype "bidirectional"))
    )
    (net (code "174") (name "unconnected-(U$1B-GPIO_125-PadP9.27)") (class "Default")
      (node (ref "U$1") (pin "P9.27") (pinfunction "GPIO_125_P9.27") (pintype "bidirectional"))
    )
    (net (code "175") (name "unconnected-(U$1B-PWR_BUT-PadP9.9)") (class "Default")
      (node (ref "U$1") (pin "P9.9") (pinfunction "PWR_BUT_P9.9") (pintype "bidirectional"))
    )
    (net (code "176") (name "unconnected-(U$1B-SYS_5V-PadP9.7)") (class "Default")
      (node (ref "U$1") (pin "P9.7") (pinfunction "SYS_5V_P9.7") (pintype "bidirectional"))
    )
    (net (code "177") (name "unconnected-(U$1B-SYS_5V-PadP9.8)") (class "Default")
      (node (ref "U$1") (pin "P9.8") (pinfunction "SYS_5V_P9.8") (pintype "bidirectional"))
    )
    (net (code "178") (name "unconnected-(U$1B-SYS_RESET~{N}-PadP9.10)") (class "Default")
      (node (ref "U$1") (pin "P9.10") (pinfunction "SYS_RESET~{N}_P9.10") (pintype "bidirectional"))
    )
    (net (code "179") (name "unconnected-(U$1B-VDD_3V3-PadP9.3)") (class "Default")
      (node (ref "U$1") (pin "P9.3") (pinfunction "VDD_3V3_P9.3") (pintype "bidirectional"))
    )
    (net (code "180") (name "unconnected-(U$1B-VDD_3V3-PadP9.4)") (class "Default")
      (node (ref "U$1") (pin "P9.4") (pinfunction "VDD_3V3_P9.4") (pintype "bidirectional"))
    )
    (net (code "181") (name "unconnected-(U$1B-VDD_5V-PadP9.5)") (class "Default")
      (node (ref "U$1") (pin "P9.5") (pinfunction "VDD_5V_P9.5") (pintype "bidirectional"))
    )
    (net (code "182") (name "unconnected-(U$1B-VDD_5V-PadP9.6)") (class "Default")
      (node (ref "U$1") (pin "P9.6") (pinfunction "VDD_5V_P9.6") (pintype "bidirectional"))
    )
    (net (code "183") (name "unconnected-(U$1B-VDD_ADC-PadP9.32)") (class "Default")
      (node (ref "U$1") (pin "P9.32") (pinfunction "VDD_ADC_P9.32") (pintype "bidirectional"))
    )
    (net (code "184") (name "unconnected-(U$3A-GPIO_8-PadP8.35)") (class "Default")
      (node (ref "U$3") (pin "P8.35") (pinfunction "GPIO_8_P8.35") (pintype "bidirectional"))
    )
    (net (code "185") (name "unconnected-(U$3A-GPIO_9-PadP8.33)") (class "Default")
      (node (ref "U$3") (pin "P8.33") (pinfunction "GPIO_9_P8.33") (pintype "bidirectional"))
    )
    (net (code "186") (name "unconnected-(U$3A-GPIO_10-PadP8.31)") (class "Default")
      (node (ref "U$3") (pin "P8.31") (pinfunction "GPIO_10_P8.31") (pintype "bidirectional"))
    )
    (net (code "187") (name "unconnected-(U$3A-GPIO_11-PadP8.32)") (class "Default")
      (node (ref "U$3") (pin "P8.32") (pinfunction "GPIO_11_P8.32") (pintype "bidirectional"))
    )
    (net (code "188") (name "unconnected-(U$3A-GPIO_22-PadP8.19)") (class "Default")
      (node (ref "U$3") (pin "P8.19") (pinfunction "GPIO_22_P8.19") (pintype "bidirectional"))
    )
    (net (code "189") (name "unconnected-(U$3A-GPIO_23-PadP8.13)") (class "Default")
      (node (ref "U$3") (pin "P8.13") (pinfunction "GPIO_23_P8.13") (pintype "bidirectional"))
    )
    (net (code "190") (name "unconnected-(U$3A-GPIO_26-PadP8.14)") (class "Default")
      (node (ref "U$3") (pin "P8.14") (pinfunction "GPIO_26_P8.14") (pintype "bidirectional"))
    )
    (net (code "191") (name "unconnected-(U$3A-GPIO_27-PadP8.17)") (class "Default")
      (node (ref "U$3") (pin "P8.17") (pinfunction "GPIO_27_P8.17") (pintype "bidirectional"))
    )
    (net (code "192") (name "unconnected-(U$3A-GPIO_32-PadP8.25)") (class "Default")
      (node (ref "U$3") (pin "P8.25") (pinfunction "GPIO_32_P8.25") (pintype "bidirectional"))
    )
    (net (code "193") (name "unconnected-(U$3A-GPIO_33-PadP8.24)") (class "Default")
      (node (ref "U$3") (pin "P8.24") (pinfunction "GPIO_33_P8.24") (pintype "bidirectional"))
    )
    (net (code "194") (name "unconnected-(U$3A-GPIO_34-PadP8.5)") (class "Default")
      (node (ref "U$3") (pin "P8.5") (pinfunction "GPIO_34_P8.5") (pintype "bidirectional"))
    )
    (net (code "195") (name "unconnected-(U$3A-GPIO_35-PadP8.6)") (class "Default")
      (node (ref "U$3") (pin "P8.6") (pinfunction "GPIO_35_P8.6") (pintype "bidirectional"))
    )
    (net (code "196") (name "unconnected-(U$3A-GPIO_36-PadP8.23)") (class "Default")
      (node (ref "U$3") (pin "P8.23") (pinfunction "GPIO_36_P8.23") (pintype "bidirectional"))
    )
    (net (code "197") (name "unconnected-(U$3A-GPIO_37-PadP8.22)") (class "Default")
      (node (ref "U$3") (pin "P8.22") (pinfunction "GPIO_37_P8.22") (pintype "bidirectional"))
    )
    (net (code "198") (name "unconnected-(U$3A-GPIO_38-PadP8.3)") (class "Default")
      (node (ref "U$3") (pin "P8.3") (pinfunction "GPIO_38_P8.3") (pintype "bidirectional"))
    )
    (net (code "199") (name "unconnected-(U$3A-GPIO_39-PadP8.4)") (class "Default")
      (node (ref "U$3") (pin "P8.4") (pinfunction "GPIO_39_P8.4") (pintype "bidirectional"))
    )
    (net (code "200") (name "unconnected-(U$3A-GPIO_44-PadP8.12)") (class "Default")
      (node (ref "U$3") (pin "P8.12") (pinfunction "GPIO_44_P8.12") (pintype "bidirectional"))
    )
    (net (code "201") (name "unconnected-(U$3A-GPIO_45-PadP8.11)") (class "Default")
      (node (ref "U$3") (pin "P8.11") (pinfunction "GPIO_45_P8.11") (pintype "bidirectional"))
    )
    (net (code "202") (name "unconnected-(U$3A-GPIO_46-PadP8.16)") (class "Default")
      (node (ref "U$3") (pin "P8.16") (pinfunction "GPIO_46_P8.16") (pintype "bidirectional"))
    )
    (net (code "203") (name "unconnected-(U$3A-GPIO_47-PadP8.15)") (class "Default")
      (node (ref "U$3") (pin "P8.15") (pinfunction "GPIO_47_P8.15") (pintype "bidirectional"))
    )
    (net (code "204") (name "unconnected-(U$3A-GPIO_61-PadP8.26)") (class "Default")
      (node (ref "U$3") (pin "P8.26") (pinfunction "GPIO_61_P8.26") (pintype "bidirectional"))
    )
    (net (code "205") (name "unconnected-(U$3A-GPIO_62-PadP8.21)") (class "Default")
      (node (ref "U$3") (pin "P8.21") (pinfunction "GPIO_62_P8.21") (pintype "bidirectional"))
    )
    (net (code "206") (name "unconnected-(U$3A-GPIO_63-PadP8.20)") (class "Default")
      (node (ref "U$3") (pin "P8.20") (pinfunction "GPIO_63_P8.20") (pintype "bidirectional"))
    )
    (net (code "207") (name "unconnected-(U$3A-GPIO_65-PadP8.18)") (class "Default")
      (node (ref "U$3") (pin "P8.18") (pinfunction "GPIO_65_P8.18") (pintype "bidirectional"))
    )
    (net (code "208") (name "unconnected-(U$3A-GPIO_66-PadP8.7)") (class "Default")
      (node (ref "U$3") (pin "P8.7") (pinfunction "GPIO_66_P8.7") (pintype "bidirectional"))
    )
    (net (code "209") (name "unconnected-(U$3A-GPIO_67-PadP8.8)") (class "Default")
      (node (ref "U$3") (pin "P8.8") (pinfunction "GPIO_67_P8.8") (pintype "bidirectional"))
    )
    (net (code "210") (name "unconnected-(U$3A-GPIO_68-PadP8.10)") (class "Default")
      (node (ref "U$3") (pin "P8.10") (pinfunction "GPIO_68_P8.10") (pintype "bidirectional"))
    )
    (net (code "211") (name "unconnected-(U$3A-GPIO_69-PadP8.9)") (class "Default")
      (node (ref "U$3") (pin "P8.9") (pinfunction "GPIO_69_P8.9") (pintype "bidirectional"))
    )
    (net (code "212") (name "unconnected-(U$3A-GPIO_70-PadP8.45)") (class "Default")
      (node (ref "U$3") (pin "P8.45") (pinfunction "GPIO_70_P8.45") (pintype "bidirectional"))
    )
    (net (code "213") (name "unconnected-(U$3A-GPIO_71-PadP8.46)") (class "Default")
      (node (ref "U$3") (pin "P8.46") (pinfunction "GPIO_71_P8.46") (pintype "bidirectional"))
    )
    (net (code "214") (name "unconnected-(U$3A-GPIO_72-PadP8.43)") (class "Default")
      (node (ref "U$3") (pin "P8.43") (pinfunction "GPIO_72_P8.43") (pintype "bidirectional"))
    )
    (net (code "215") (name "unconnected-(U$3A-GPIO_73-PadP8.44)") (class "Default")
      (node (ref "U$3") (pin "P8.44") (pinfunction "GPIO_73_P8.44") (pintype "bidirectional"))
    )
    (net (code "216") (name "unconnected-(U$3A-GPIO_74-PadP8.41)") (class "Default")
      (node (ref "U$3") (pin "P8.41") (pinfunction "GPIO_74_P8.41") (pintype "bidirectional"))
    )
    (net (code "217") (name "unconnected-(U$3A-GPIO_75-PadP8.42)") (class "Default")
      (node (ref "U$3") (pin "P8.42") (pinfunction "GPIO_75_P8.42") (pintype "bidirectional"))
    )
    (net (code "218") (name "unconnected-(U$3A-GPIO_76-PadP8.39)") (class "Default")
      (node (ref "U$3") (pin "P8.39") (pinfunction "GPIO_76_P8.39") (pintype "bidirectional"))
    )
    (net (code "219") (name "unconnected-(U$3A-GPIO_77-PadP8.40)") (class "Default")
      (node (ref "U$3") (pin "P8.40") (pinfunction "GPIO_77_P8.40") (pintype "bidirectional"))
    )
    (net (code "220") (name "unconnected-(U$3A-GPIO_78-PadP8.37)") (class "Default")
      (node (ref "U$3") (pin "P8.37") (pinfunction "GPIO_78_P8.37") (pintype "bidirectional"))
    )
    (net (code "221") (name "unconnected-(U$3A-GPIO_79-PadP8.38)") (class "Default")
      (node (ref "U$3") (pin "P8.38") (pinfunction "GPIO_79_P8.38") (pintype "bidirectional"))
    )
    (net (code "222") (name "unconnected-(U$3A-GPIO_80-PadP8.36)") (class "Default")
      (node (ref "U$3") (pin "P8.36") (pinfunction "GPIO_80_P8.36") (pintype "bidirectional"))
    )
    (net (code "223") (name "unconnected-(U$3A-GPIO_81-PadP8.34)") (class "Default")
      (node (ref "U$3") (pin "P8.34") (pinfunction "GPIO_81_P8.34") (pintype "bidirectional"))
    )
    (net (code "224") (name "unconnected-(U$3A-GPIO_86-PadP8.27)") (class "Default")
      (node (ref "U$3") (pin "P8.27") (pinfunction "GPIO_86_P8.27") (pintype "bidirectional"))
    )
    (net (code "225") (name "unconnected-(U$3A-GPIO_87-PadP8.29)") (class "Default")
      (node (ref "U$3") (pin "P8.29") (pinfunction "GPIO_87_P8.29") (pintype "bidirectional"))
    )
    (net (code "226") (name "unconnected-(U$3A-GPIO_88-PadP8.28)") (class "Default")
      (node (ref "U$3") (pin "P8.28") (pinfunction "GPIO_88_P8.28") (pintype "bidirectional"))
    )
    (net (code "227") (name "unconnected-(U$3A-GPIO_89-PadP8.30)") (class "Default")
      (node (ref "U$3") (pin "P8.30") (pinfunction "GPIO_89_P8.30") (pintype "bidirectional"))
    )
    (net (code "228") (name "unconnected-(U$3B-AIN0-PadP9.39)") (class "Default")
      (node (ref "U$3") (pin "P9.39") (pinfunction "AIN0_P9.39") (pintype "bidirectional"))
    )
    (net (code "229") (name "unconnected-(U$3B-AIN1-PadP9.40)") (class "Default")
      (node (ref "U$3") (pin "P9.40") (pinfunction "AIN1_P9.40") (pintype "bidirectional"))
    )
    (net (code "230") (name "unconnected-(U$3B-AIN2-PadP9.37)") (class "Default")
      (node (ref "U$3") (pin "P9.37") (pinfunction "AIN2_P9.37") (pintype "bidirectional"))
    )
    (net (code "231") (name "unconnected-(U$3B-AIN3-PadP9.38)") (class "Default")
      (node (ref "U$3") (pin "P9.38") (pinfunction "AIN3_P9.38") (pintype "bidirectional"))
    )
    (net (code "232") (name "unconnected-(U$3B-AIN4-PadP9.33)") (class "Default")
      (node (ref "U$3") (pin "P9.33") (pinfunction "AIN4_P9.33") (pintype "bidirectional"))
    )
    (net (code "233") (name "unconnected-(U$3B-AIN5-PadP9.36)") (class "Default")
      (node (ref "U$3") (pin "P9.36") (pinfunction "AIN5_P9.36") (pintype "bidirectional"))
    )
    (net (code "234") (name "unconnected-(U$3B-AIN6-PadP9.35)") (class "Default")
      (node (ref "U$3") (pin "P9.35") (pinfunction "AIN6_P9.35") (pintype "bidirectional"))
    )
    (net (code "235") (name "unconnected-(U$3B-GNDA_ADC-PadP9.34)") (class "Default")
      (node (ref "U$3") (pin "P9.34") (pinfunction "GNDA_ADC_P9.34") (pintype "bidirectional"))
    )
    (net (code "236") (name "unconnected-(U$3B-GPIO_2-PadP9.22)") (class "Default")
      (node (ref "U$3") (pin "P9.22") (pinfunction "GPIO_2_P9.22") (pintype "bidirectional"))
    )
    (net (code "237") (name "unconnected-(U$3B-GPIO_3-PadP9.21)") (class "Default")
      (node (ref "U$3") (pin "P9.21") (pinfunction "GPIO_3_P9.21") (pintype "bidirectional"))
    )
    (net (code "238") (name "unconnected-(U$3B-GPIO_4-PadP9.17)") (class "Default")
      (node (ref "U$3") (pin "P9.17") (pinfunction "GPIO_4_P9.17") (pintype "bidirectional"))
    )
    (net (code "239") (name "unconnected-(U$3B-GPIO_5-PadP9.18)") (class "Default")
      (node (ref "U$3") (pin "P9.18") (pinfunction "GPIO_5_P9.18") (pintype "bidirectional"))
    )
    (net (code "240") (name "unconnected-(U$3B-GPIO_7-PadP9.42)") (class "Default")
      (node (ref "U$3") (pin "P9.42") (pinfunction "GPIO_7_P9.42") (pintype "bidirectional"))
    )
    (net (code "241") (name "unconnected-(U$3B-GPIO_14-PadP9.26)") (class "Default")
      (node (ref "U$3") (pin "P9.26") (pinfunction "GPIO_14_P9.26") (pintype "bidirectional"))
    )
    (net (code "242") (name "unconnected-(U$3B-GPIO_15-PadP9.24)") (class "Default")
      (node (ref "U$3") (pin "P9.24") (pinfunction "GPIO_15_P9.24") (pintype "bidirectional"))
    )
    (net (code "243") (name "unconnected-(U$3B-GPIO_20-PadP9.41)") (class "Default")
      (node (ref "U$3") (pin "P9.41") (pinfunction "GPIO_20_P9.41") (pintype "bidirectional"))
    )
    (net (code "244") (name "unconnected-(U$3B-GPIO_30-PadP9.11)") (class "Default")
      (node (ref "U$3") (pin "P9.11") (pinfunction "GPIO_30_P9.11") (pintype "bidirectional"))
    )
    (net (code "245") (name "unconnected-(U$3B-GPIO_31-PadP9.13)") (class "Default")
      (node (ref "U$3") (pin "P9.13") (pinfunction "GPIO_31_P9.13") (pintype "bidirectional"))
    )
    (net (code "246") (name "unconnected-(U$3B-GPIO_40-PadP9.14)") (class "Default")
      (node (ref "U$3") (pin "P9.14") (pinfunction "GPIO_40_P9.14") (pintype "bidirectional"))
    )
    (net (code "247") (name "unconnected-(U$3B-GPIO_48-PadP9.15)") (class "Default")
      (node (ref "U$3") (pin "P9.15") (pinfunction "GPIO_48_P9.15") (pintype "bidirectional"))
    )
    (net (code "248") (name "unconnected-(U$3B-GPIO_49-PadP9.23)") (class "Default")
      (node (ref "U$3") (pin "P9.23") (pinfunction "GPIO_49_P9.23") (pintype "bidirectional"))
    )
    (net (code "249") (name "unconnected-(U$3B-GPIO_51-PadP9.16)") (class "Default")
      (node (ref "U$3") (pin "P9.16") (pinfunction "GPIO_51_P9.16") (pintype "bidirectional"))
    )
    (net (code "250") (name "unconnected-(U$3B-GPIO_60-PadP9.12)") (class "Default")
      (node (ref "U$3") (pin "P9.12") (pinfunction "GPIO_60_P9.12") (pintype "bidirectional"))
    )
    (net (code "251") (name "unconnected-(U$3B-GPIO_117-PadP9.25)") (class "Default")
      (node (ref "U$3") (pin "P9.25") (pinfunction "GPIO_117_P9.25") (pintype "bidirectional"))
    )
    (net (code "252") (name "unconnected-(U$3B-GPIO_120-PadP9.31)") (class "Default")
      (node (ref "U$3") (pin "P9.31") (pinfunction "GPIO_120_P9.31") (pintype "bidirectional"))
    )
    (net (code "253") (name "unconnected-(U$3B-GPIO_121-PadP9.29)") (class "Default")
      (node (ref "U$3") (pin "P9.29") (pinfunction "GPIO_121_P9.29") (pintype "bidirectional"))
    )
    (net (code "254") (name "unconnected-(U$3B-GPIO_122-PadP9.30)") (class "Default")
      (node (ref "U$3") (pin "P9.30") (pinfunction "GPIO_122_P9.30") (pintype "bidirectional"))
    )
    (net (code "255") (name "unconnected-(U$3B-GPIO_123-PadP9.28)") (class "Default")
      (node (ref "U$3") (pin "P9.28") (pinfunction "GPIO_123_P9.28") (pintype "bidirectional"))
    )
    (net (code "256") (name "unconnected-(U$3B-GPIO_125-PadP9.27)") (class "Default")
      (node (ref "U$3") (pin "P9.27") (pinfunction "GPIO_125_P9.27") (pintype "bidirectional"))
    )
    (net (code "257") (name "unconnected-(U$3B-I2C2_SCL-PadP9.19)") (class "Default")
      (node (ref "U$3") (pin "P9.19") (pinfunction "I2C2_SCL_P9.19") (pintype "bidirectional"))
    )
    (net (code "258") (name "unconnected-(U$3B-I2C2_SDA-PadP9.20)") (class "Default")
      (node (ref "U$3") (pin "P9.20") (pinfunction "I2C2_SDA_P9.20") (pintype "bidirectional"))
    )
    (net (code "259") (name "unconnected-(U$3B-PWR_BUT-PadP9.9)") (class "Default")
      (node (ref "U$3") (pin "P9.9") (pinfunction "PWR_BUT_P9.9") (pintype "bidirectional"))
    )
    (net (code "260") (name "unconnected-(U$3B-SYS_5V-PadP9.7)") (class "Default")
      (node (ref "U$3") (pin "P9.7") (pinfunction "SYS_5V_P9.7") (pintype "bidirectional"))
    )
    (net (code "261") (name "unconnected-(U$3B-SYS_5V-PadP9.8)") (class "Default")
      (node (ref "U$3") (pin "P9.8") (pinfunction "SYS_5V_P9.8") (pintype "bidirectional"))
    )
    (net (code "262") (name "unconnected-(U$3B-SYS_RESET~{N}-PadP9.10)") (class "Default")
      (node (ref "U$3") (pin "P9.10") (pinfunction "SYS_RESET~{N}_P9.10") (pintype "bidirectional"))
    )
    (net (code "263") (name "unconnected-(U$3B-VDD_3V3-PadP9.3)") (class "Default")
      (node (ref "U$3") (pin "P9.3") (pinfunction "VDD_3V3_P9.3") (pintype "bidirectional"))
    )
    (net (code "264") (name "unconnected-(U$3B-VDD_3V3-PadP9.4)") (class "Default")
      (node (ref "U$3") (pin "P9.4") (pinfunction "VDD_3V3_P9.4") (pintype "bidirectional"))
    )
    (net (code "265") (name "unconnected-(U$3B-VDD_ADC-PadP9.32)") (class "Default")
      (node (ref "U$3") (pin "P9.32") (pinfunction "VDD_ADC_P9.32") (pintype "bidirectional"))
    )
    (net (code "266") (name "unconnected-(U3-OUT-Pad2)") (class "Default")
      (node (ref "U3") (pin "2") (pinfunction "OUT_2") (pintype "output"))
    )
  )
)
